# Sheet2.net
KiCad netlist of a schematic drawn in Altium Designer
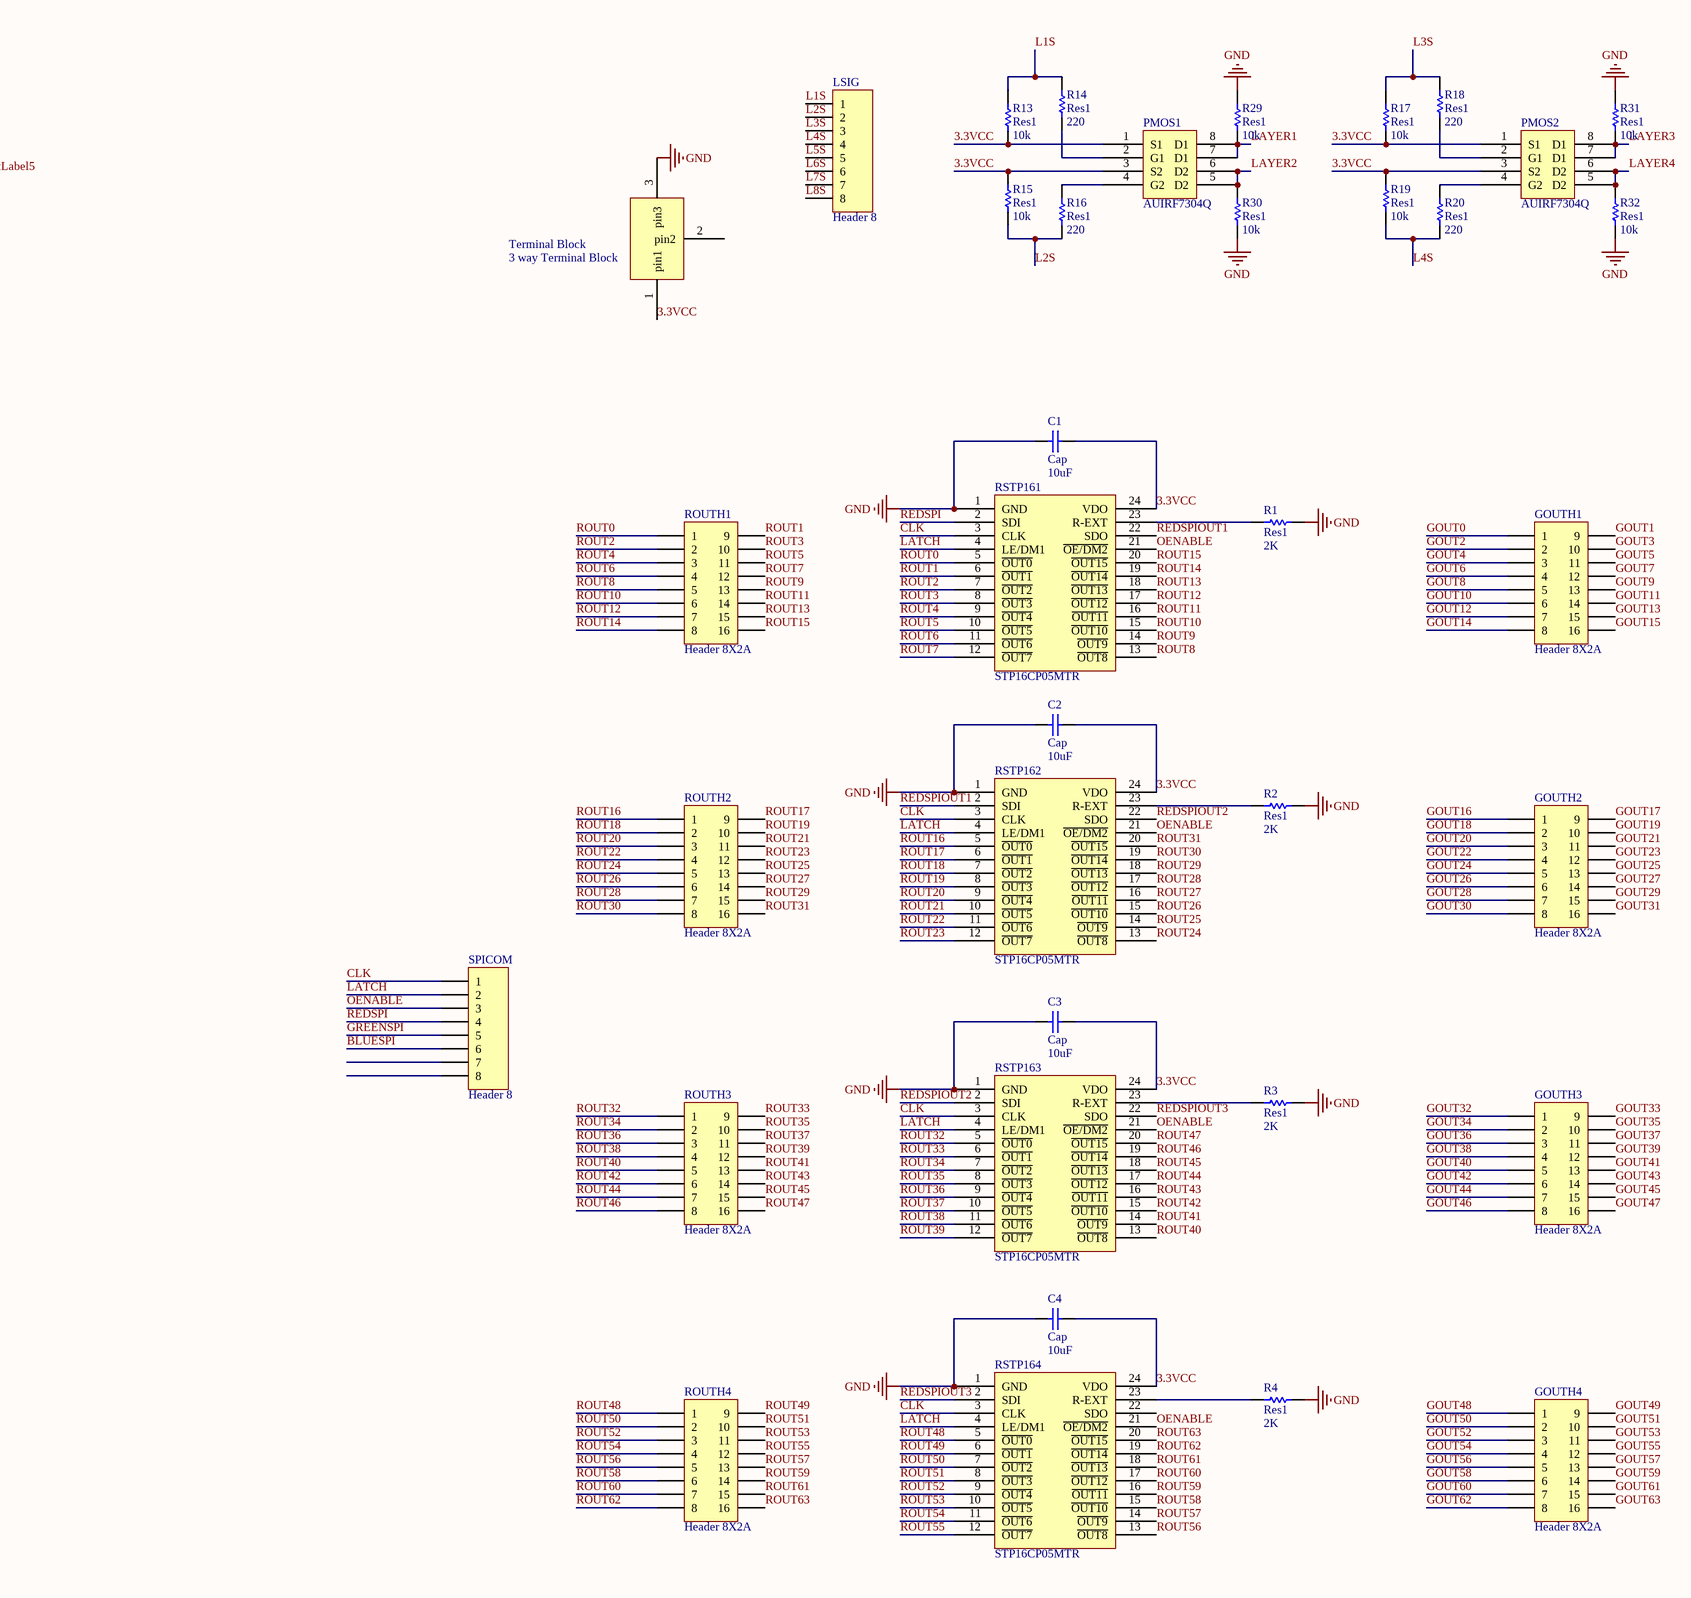
[diagram p0: Sheet2.SchDoc, left]
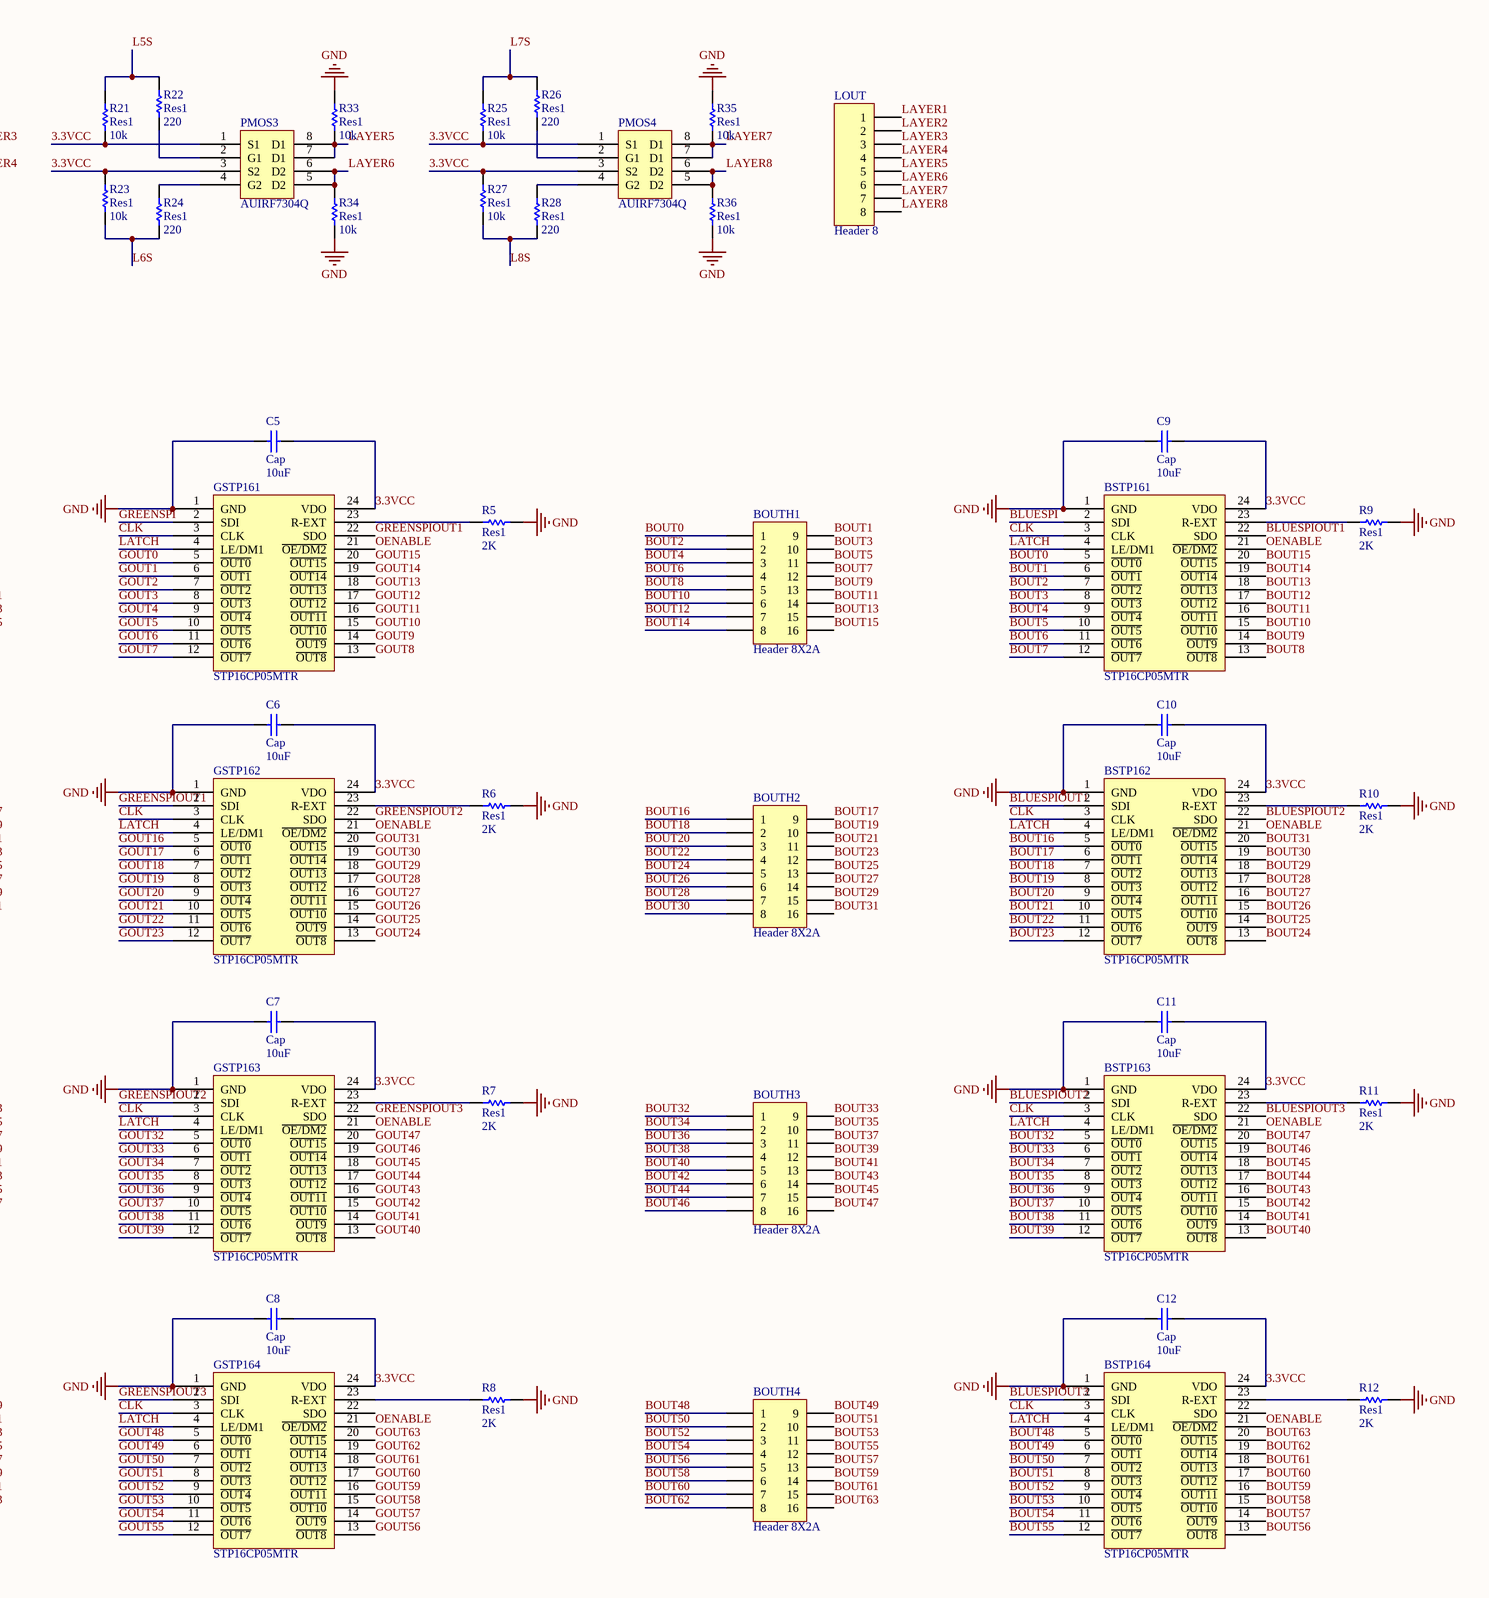
[diagram p1: Sheet2.SchDoc, right]

(export (version "E")
  (design (tool "Eeschema 10.0.6"))
  (components
    (comp (ref "BOUTH1")
      (value "Header 8X2A")
      (footprint "HDR2X8_CEN")
      (description "Header, 8-Pin, Dual row")
      (fields (field (name "PUBLISHER") "Altium Limited"))
      (libsource (lib "Miscellaneous Connectors") (part "Header 8X2A"))
    )
    (comp (ref "BOUTH2")
      (value "Header 8X2A")
      (footprint "HDR2X8_CEN")
      (description "Header, 8-Pin, Dual row")
      (fields (field (name "PUBLISHER") "Altium Limited"))
      (libsource (lib "Miscellaneous Connectors") (part "Header 8X2A"))
    )
    (comp (ref "BOUTH3")
      (value "Header 8X2A")
      (footprint "HDR2X8_CEN")
      (description "Header, 8-Pin, Dual row")
      (fields (field (name "PUBLISHER") "Altium Limited"))
      (libsource (lib "Miscellaneous Connectors") (part "Header 8X2A"))
    )
    (comp (ref "BOUTH4")
      (value "Header 8X2A")
      (footprint "HDR2X8_CEN")
      (description "Header, 8-Pin, Dual row")
      (fields (field (name "PUBLISHER") "Altium Limited"))
      (libsource (lib "Miscellaneous Connectors") (part "Header 8X2A"))
    )
    (comp (ref "BSTP161")
      (value "STP16CP05MTR")
      (footprint "STP16CP05MTR-24N")
      (libsource (lib "STP16CP05MTR") (part "STP16CP05MTR"))
    )
    (comp (ref "BSTP162")
      (value "STP16CP05MTR")
      (footprint "STP16CP05MTR-24N")
      (libsource (lib "STP16CP05MTR") (part "STP16CP05MTR"))
    )
    (comp (ref "BSTP163")
      (value "STP16CP05MTR")
      (footprint "STP16CP05MTR-24N")
      (libsource (lib "STP16CP05MTR") (part "STP16CP05MTR"))
    )
    (comp (ref "BSTP164")
      (value "STP16CP05MTR")
      (footprint "STP16CP05MTR-24N")
      (libsource (lib "STP16CP05MTR") (part "STP16CP05MTR"))
    )
    (comp (ref "C1")
      (value "Cap")
      (footprint "RAD-0.3")
      (description "Capacitor")
      (fields (field (name "ALTIUM_VALUE") "10uF") (field (name "PUBLISHER") "Altium Limited"))
      (libsource (lib "Miscellaneous Devices") (part "Cap"))
    )
    (comp (ref "C2")
      (value "Cap")
      (footprint "RAD-0.3")
      (description "Capacitor")
      (fields (field (name "ALTIUM_VALUE") "10uF") (field (name "PUBLISHER") "Altium Limited"))
      (libsource (lib "Miscellaneous Devices") (part "Cap"))
    )
    (comp (ref "C3")
      (value "Cap")
      (footprint "RAD-0.3")
      (description "Capacitor")
      (fields (field (name "ALTIUM_VALUE") "10uF") (field (name "PUBLISHER") "Altium Limited"))
      (libsource (lib "Miscellaneous Devices") (part "Cap"))
    )
    (comp (ref "C4")
      (value "Cap")
      (footprint "RAD-0.3")
      (description "Capacitor")
      (fields (field (name "ALTIUM_VALUE") "10uF") (field (name "PUBLISHER") "Altium Limited"))
      (libsource (lib "Miscellaneous Devices") (part "Cap"))
    )
    (comp (ref "C5")
      (value "Cap")
      (footprint "RAD-0.3")
      (description "Capacitor")
      (fields (field (name "ALTIUM_VALUE") "10uF") (field (name "PUBLISHER") "Altium Limited"))
      (libsource (lib "Miscellaneous Devices") (part "Cap"))
    )
    (comp (ref "C6")
      (value "Cap")
      (footprint "RAD-0.3")
      (description "Capacitor")
      (fields (field (name "ALTIUM_VALUE") "10uF") (field (name "PUBLISHER") "Altium Limited"))
      (libsource (lib "Miscellaneous Devices") (part "Cap"))
    )
    (comp (ref "C7")
      (value "Cap")
      (footprint "RAD-0.3")
      (description "Capacitor")
      (fields (field (name "ALTIUM_VALUE") "10uF") (field (name "PUBLISHER") "Altium Limited"))
      (libsource (lib "Miscellaneous Devices") (part "Cap"))
    )
    (comp (ref "C8")
      (value "Cap")
      (footprint "RAD-0.3")
      (description "Capacitor")
      (fields (field (name "ALTIUM_VALUE") "10uF") (field (name "PUBLISHER") "Altium Limited"))
      (libsource (lib "Miscellaneous Devices") (part "Cap"))
    )
    (comp (ref "C9")
      (value "Cap")
      (footprint "RAD-0.3")
      (description "Capacitor")
      (fields (field (name "ALTIUM_VALUE") "10uF") (field (name "PUBLISHER") "Altium Limited"))
      (libsource (lib "Miscellaneous Devices") (part "Cap"))
    )
    (comp (ref "C10")
      (value "Cap")
      (footprint "RAD-0.3")
      (description "Capacitor")
      (fields (field (name "ALTIUM_VALUE") "10uF") (field (name "PUBLISHER") "Altium Limited"))
      (libsource (lib "Miscellaneous Devices") (part "Cap"))
    )
    (comp (ref "C11")
      (value "Cap")
      (footprint "RAD-0.3")
      (description "Capacitor")
      (fields (field (name "ALTIUM_VALUE") "10uF") (field (name "PUBLISHER") "Altium Limited"))
      (libsource (lib "Miscellaneous Devices") (part "Cap"))
    )
    (comp (ref "C12")
      (value "Cap")
      (footprint "RAD0.2A")
      (description "Capacitor")
      (fields (field (name "ALTIUM_VALUE") "10uF") (field (name "PUBLISHER") "Altium Limited"))
      (libsource (lib "Miscellaneous Devices") (part "Cap"))
    )
    (comp (ref "GOUTH1")
      (value "Header 8X2A")
      (footprint "HDR2X8_CEN")
      (description "Header, 8-Pin, Dual row")
      (fields (field (name "PUBLISHER") "Altium Limited"))
      (libsource (lib "Miscellaneous Connectors") (part "Header 8X2A"))
    )
    (comp (ref "GOUTH2")
      (value "Header 8X2A")
      (footprint "HDR2X8_CEN")
      (description "Header, 8-Pin, Dual row")
      (fields (field (name "PUBLISHER") "Altium Limited"))
      (libsource (lib "Miscellaneous Connectors") (part "Header 8X2A"))
    )
    (comp (ref "GOUTH3")
      (value "Header 8X2A")
      (footprint "HDR2X8_CEN")
      (description "Header, 8-Pin, Dual row")
      (fields (field (name "PUBLISHER") "Altium Limited"))
      (libsource (lib "Miscellaneous Connectors") (part "Header 8X2A"))
    )
    (comp (ref "GOUTH4")
      (value "Header 8X2A")
      (footprint "HDR2X8_CEN")
      (description "Header, 8-Pin, Dual row")
      (fields (field (name "PUBLISHER") "Altium Limited"))
      (libsource (lib "Miscellaneous Connectors") (part "Header 8X2A"))
    )
    (comp (ref "GSTP161")
      (value "STP16CP05MTR")
      (footprint "STP16CP05MTR-24N")
      (libsource (lib "STP16CP05MTR") (part "STP16CP05MTR"))
    )
    (comp (ref "GSTP162")
      (value "STP16CP05MTR")
      (footprint "STP16CP05MTR-24N")
      (libsource (lib "STP16CP05MTR") (part "STP16CP05MTR"))
    )
    (comp (ref "GSTP163")
      (value "STP16CP05MTR")
      (footprint "STP16CP05MTR-24N")
      (libsource (lib "STP16CP05MTR") (part "STP16CP05MTR"))
    )
    (comp (ref "GSTP164")
      (value "STP16CP05MTR")
      (footprint "STP16CP05MTR-24N")
      (libsource (lib "STP16CP05MTR") (part "STP16CP05MTR"))
    )
    (comp (ref "LOUT")
      (value "Header 8")
      (footprint "HDR1X8")
      (description "Header, 8-Pin")
      (fields (field (name "PUBLISHER") "Altium Limited"))
      (libsource (lib "Miscellaneous Connectors") (part "Header 8"))
    )
    (comp (ref "LSIG")
      (value "Header 8")
      (footprint "HDR1X8")
      (description "Header, 8-Pin")
      (fields (field (name "PUBLISHER") "Altium Limited"))
      (libsource (lib "") (part "Header 8_1"))
    )
    (comp (ref "PMOS1")
      (value "AUIRF7304Q")
      (footprint "AUIRF7304Q")
      (libsource (lib "AUIRF7304Q") (part "Component_1"))
    )
    (comp (ref "PMOS2")
      (value "AUIRF7304Q")
      (footprint "AUIRF7304Q")
      (libsource (lib "AUIRF7304Q") (part "Component_1"))
    )
    (comp (ref "PMOS3")
      (value "AUIRF7304Q")
      (footprint "AUIRF7304Q")
      (libsource (lib "AUIRF7304Q") (part "Component_1"))
    )
    (comp (ref "PMOS4")
      (value "AUIRF7304Q")
      (footprint "AUIRF7304Q")
      (libsource (lib "AUIRF7304Q") (part "Component_1"))
    )
    (comp (ref "R1")
      (value "Res1")
      (footprint "AXIAL-0.3")
      (description "Resistor")
      (fields (field (name "ALTIUM_VALUE") "2K") (field (name "PUBLISHER") "Altium Limited"))
      (libsource (lib "Miscellaneous Devices") (part "Res1"))
    )
    (comp (ref "R2")
      (value "Res1")
      (footprint "AXIAL-0.3")
      (description "Resistor")
      (fields (field (name "ALTIUM_VALUE") "2K") (field (name "PUBLISHER") "Altium Limited"))
      (libsource (lib "Miscellaneous Devices") (part "Res1"))
    )
    (comp (ref "R3")
      (value "Res1")
      (footprint "AXIAL-0.3")
      (description "Resistor")
      (fields (field (name "ALTIUM_VALUE") "2K") (field (name "PUBLISHER") "Altium Limited"))
      (libsource (lib "Miscellaneous Devices") (part "Res1"))
    )
    (comp (ref "R4")
      (value "Res1")
      (footprint "AXIAL-0.3")
      (description "Resistor")
      (fields (field (name "ALTIUM_VALUE") "2K") (field (name "PUBLISHER") "Altium Limited"))
      (libsource (lib "Miscellaneous Devices") (part "Res1"))
    )
    (comp (ref "R5")
      (value "Res1")
      (footprint "AXIAL-0.3")
      (description "Resistor")
      (fields (field (name "ALTIUM_VALUE") "2K") (field (name "PUBLISHER") "Altium Limited"))
      (libsource (lib "Miscellaneous Devices") (part "Res1"))
    )
    (comp (ref "R6")
      (value "Res1")
      (footprint "AXIAL-0.3")
      (description "Resistor")
      (fields (field (name "ALTIUM_VALUE") "2K") (field (name "PUBLISHER") "Altium Limited"))
      (libsource (lib "Miscellaneous Devices") (part "Res1"))
    )
    (comp (ref "R7")
      (value "Res1")
      (footprint "AXIAL-0.3")
      (description "Resistor")
      (fields (field (name "ALTIUM_VALUE") "2K") (field (name "PUBLISHER") "Altium Limited"))
      (libsource (lib "Miscellaneous Devices") (part "Res1"))
    )
    (comp (ref "R8")
      (value "Res1")
      (footprint "AXIAL-0.3")
      (description "Resistor")
      (fields (field (name "ALTIUM_VALUE") "2K") (field (name "PUBLISHER") "Altium Limited"))
      (libsource (lib "Miscellaneous Devices") (part "Res1"))
    )
    (comp (ref "R9")
      (value "Res1")
      (footprint "AXIAL-0.3")
      (description "Resistor")
      (fields (field (name "ALTIUM_VALUE") "2K") (field (name "PUBLISHER") "Altium Limited"))
      (libsource (lib "Miscellaneous Devices") (part "Res1"))
    )
    (comp (ref "R10")
      (value "Res1")
      (footprint "AXIAL-0.3")
      (description "Resistor")
      (fields (field (name "ALTIUM_VALUE") "2K") (field (name "PUBLISHER") "Altium Limited"))
      (libsource (lib "Miscellaneous Devices") (part "Res1"))
    )
    (comp (ref "R11")
      (value "Res1")
      (footprint "AXIAL-0.3")
      (description "Resistor")
      (fields (field (name "ALTIUM_VALUE") "2K") (field (name "PUBLISHER") "Altium Limited"))
      (libsource (lib "Miscellaneous Devices") (part "Res1"))
    )
    (comp (ref "R12")
      (value "Res1")
      (footprint "AXIAL0.4")
      (description "Resistor")
      (fields (field (name "ALTIUM_VALUE") "2K") (field (name "PUBLISHER") "Altium Limited"))
      (libsource (lib "Miscellaneous Devices") (part "Res1"))
    )
    (comp (ref "R13")
      (value "Res1")
      (footprint "AXIAL-0.3")
      (description "Resistor")
      (fields (field (name "ALTIUM_VALUE") "10k") (field (name "PUBLISHER") "Altium Limited"))
      (libsource (lib "Miscellaneous Devices") (part "Res1"))
    )
    (comp (ref "R14")
      (value "Res1")
      (footprint "AXIAL-0.3")
      (description "Resistor")
      (fields (field (name "ALTIUM_VALUE") "220") (field (name "PUBLISHER") "Altium Limited"))
      (libsource (lib "Miscellaneous Devices") (part "Res1"))
    )
    (comp (ref "R15")
      (value "Res1")
      (footprint "AXIAL-0.3")
      (description "Resistor")
      (fields (field (name "ALTIUM_VALUE") "10k") (field (name "PUBLISHER") "Altium Limited"))
      (libsource (lib "Miscellaneous Devices") (part "Res1"))
    )
    (comp (ref "R16")
      (value "Res1")
      (footprint "AXIAL-0.3")
      (description "Resistor")
      (fields (field (name "ALTIUM_VALUE") "220") (field (name "PUBLISHER") "Altium Limited"))
      (libsource (lib "Miscellaneous Devices") (part "Res1"))
    )
    (comp (ref "R17")
      (value "Res1")
      (footprint "AXIAL-0.3")
      (description "Resistor")
      (fields (field (name "ALTIUM_VALUE") "10k") (field (name "PUBLISHER") "Altium Limited"))
      (libsource (lib "Miscellaneous Devices") (part "Res1"))
    )
    (comp (ref "R18")
      (value "Res1")
      (footprint "AXIAL-0.3")
      (description "Resistor")
      (fields (field (name "ALTIUM_VALUE") "220") (field (name "PUBLISHER") "Altium Limited"))
      (libsource (lib "Miscellaneous Devices") (part "Res1"))
    )
    (comp (ref "R19")
      (value "Res1")
      (footprint "AXIAL-0.3")
      (description "Resistor")
      (fields (field (name "ALTIUM_VALUE") "10k") (field (name "PUBLISHER") "Altium Limited"))
      (libsource (lib "Miscellaneous Devices") (part "Res1"))
    )
    (comp (ref "R20")
      (value "Res1")
      (footprint "AXIAL-0.3")
      (description "Resistor")
      (fields (field (name "ALTIUM_VALUE") "220") (field (name "PUBLISHER") "Altium Limited"))
      (libsource (lib "Miscellaneous Devices") (part "Res1"))
    )
    (comp (ref "R21")
      (value "Res1")
      (footprint "AXIAL-0.3")
      (description "Resistor")
      (fields (field (name "ALTIUM_VALUE") "10k") (field (name "PUBLISHER") "Altium Limited"))
      (libsource (lib "Miscellaneous Devices") (part "Res1"))
    )
    (comp (ref "R22")
      (value "Res1")
      (footprint "AXIAL-0.3")
      (description "Resistor")
      (fields (field (name "ALTIUM_VALUE") "220") (field (name "PUBLISHER") "Altium Limited"))
      (libsource (lib "Miscellaneous Devices") (part "Res1"))
    )
    (comp (ref "R23")
      (value "Res1")
      (footprint "AXIAL-0.3")
      (description "Resistor")
      (fields (field (name "ALTIUM_VALUE") "10k") (field (name "PUBLISHER") "Altium Limited"))
      (libsource (lib "Miscellaneous Devices") (part "Res1"))
    )
    (comp (ref "R24")
      (value "Res1")
      (footprint "AXIAL-0.3")
      (description "Resistor")
      (fields (field (name "ALTIUM_VALUE") "220") (field (name "PUBLISHER") "Altium Limited"))
      (libsource (lib "Miscellaneous Devices") (part "Res1"))
    )
    (comp (ref "R25")
      (value "Res1")
      (footprint "AXIAL-0.3")
      (description "Resistor")
      (fields (field (name "ALTIUM_VALUE") "10k") (field (name "PUBLISHER") "Altium Limited"))
      (libsource (lib "Miscellaneous Devices") (part "Res1"))
    )
    (comp (ref "R26")
      (value "Res1")
      (footprint "AXIAL-0.3")
      (description "Resistor")
      (fields (field (name "ALTIUM_VALUE") "220") (field (name "PUBLISHER") "Altium Limited"))
      (libsource (lib "Miscellaneous Devices") (part "Res1"))
    )
    (comp (ref "R27")
      (value "Res1")
      (footprint "AXIAL-0.3")
      (description "Resistor")
      (fields (field (name "ALTIUM_VALUE") "10k") (field (name "PUBLISHER") "Altium Limited"))
      (libsource (lib "Miscellaneous Devices") (part "Res1"))
    )
    (comp (ref "R28")
      (value "Res1")
      (footprint "AXIAL-0.3")
      (description "Resistor")
      (fields (field (name "ALTIUM_VALUE") "220") (field (name "PUBLISHER") "Altium Limited"))
      (libsource (lib "Miscellaneous Devices") (part "Res1"))
    )
    (comp (ref "R29")
      (value "Res1")
      (footprint "AXIAL-0.3")
      (description "Resistor")
      (fields (field (name "ALTIUM_VALUE") "10k") (field (name "PUBLISHER") "Altium Limited"))
      (libsource (lib "Miscellaneous Devices") (part "Res1"))
    )
    (comp (ref "R30")
      (value "Res1")
      (footprint "AXIAL-0.3")
      (description "Resistor")
      (fields (field (name "ALTIUM_VALUE") "10k") (field (name "PUBLISHER") "Altium Limited"))
      (libsource (lib "Miscellaneous Devices") (part "Res1"))
    )
    (comp (ref "R31")
      (value "Res1")
      (footprint "AXIAL-0.3")
      (description "Resistor")
      (fields (field (name "ALTIUM_VALUE") "10k") (field (name "PUBLISHER") "Altium Limited"))
      (libsource (lib "Miscellaneous Devices") (part "Res1"))
    )
    (comp (ref "R32")
      (value "Res1")
      (footprint "AXIAL-0.3")
      (description "Resistor")
      (fields (field (name "ALTIUM_VALUE") "10k") (field (name "PUBLISHER") "Altium Limited"))
      (libsource (lib "Miscellaneous Devices") (part "Res1"))
    )
    (comp (ref "R33")
      (value "Res1")
      (footprint "AXIAL-0.3")
      (description "Resistor")
      (fields (field (name "ALTIUM_VALUE") "10k") (field (name "PUBLISHER") "Altium Limited"))
      (libsource (lib "Miscellaneous Devices") (part "Res1"))
    )
    (comp (ref "R34")
      (value "Res1")
      (footprint "AXIAL-0.3")
      (description "Resistor")
      (fields (field (name "ALTIUM_VALUE") "10k") (field (name "PUBLISHER") "Altium Limited"))
      (libsource (lib "Miscellaneous Devices") (part "Res1"))
    )
    (comp (ref "R35")
      (value "Res1")
      (footprint "AXIAL-0.3")
      (description "Resistor")
      (fields (field (name "ALTIUM_VALUE") "10k") (field (name "PUBLISHER") "Altium Limited"))
      (libsource (lib "Miscellaneous Devices") (part "Res1"))
    )
    (comp (ref "R36")
      (value "Res1")
      (footprint "AXIAL-0.3")
      (description "Resistor")
      (fields (field (name "ALTIUM_VALUE") "10k") (field (name "PUBLISHER") "Altium Limited"))
      (libsource (lib "Miscellaneous Devices") (part "Res1"))
    )
    (comp (ref "ROUTH1")
      (value "Header 8X2A")
      (footprint "HDR2X8_CEN")
      (description "Header, 8-Pin, Dual row")
      (fields (field (name "PUBLISHER") "Altium Limited"))
      (libsource (lib "Miscellaneous Connectors") (part "Header 8X2A"))
    )
    (comp (ref "ROUTH2")
      (value "Header 8X2A")
      (footprint "HDR2X8_CEN")
      (description "Header, 8-Pin, Dual row")
      (fields (field (name "PUBLISHER") "Altium Limited"))
      (libsource (lib "Miscellaneous Connectors") (part "Header 8X2A"))
    )
    (comp (ref "ROUTH3")
      (value "Header 8X2A")
      (footprint "HDR2X8_CEN")
      (description "Header, 8-Pin, Dual row")
      (fields (field (name "PUBLISHER") "Altium Limited"))
      (libsource (lib "Miscellaneous Connectors") (part "Header 8X2A"))
    )
    (comp (ref "ROUTH4")
      (value "Header 8X2A")
      (footprint "HDR2X8_CEN")
      (description "Header, 8-Pin, Dual row")
      (fields (field (name "PUBLISHER") "Altium Limited"))
      (libsource (lib "Miscellaneous Connectors") (part "Header 8X2A"))
    )
    (comp (ref "RSTP161")
      (value "STP16CP05MTR")
      (footprint "STP16CP05MTR-24N")
      (libsource (lib "STP16CP05MTR") (part "STP16CP05MTR"))
    )
    (comp (ref "RSTP162")
      (value "STP16CP05MTR")
      (footprint "STP16CP05MTR-24N")
      (libsource (lib "STP16CP05MTR") (part "STP16CP05MTR"))
    )
    (comp (ref "RSTP163")
      (value "STP16CP05MTR")
      (footprint "STP16CP05MTR-24N")
      (libsource (lib "STP16CP05MTR") (part "STP16CP05MTR"))
    )
    (comp (ref "RSTP164")
      (value "STP16CP05MTR")
      (footprint "STP16CP05MTR-24N")
      (libsource (lib "STP16CP05MTR") (part "STP16CP05MTR"))
    )
    (comp (ref "SPICOM")
      (value "Header 8")
      (footprint "HDR1X8")
      (description "Header, 8-Pin")
      (fields (field (name "PUBLISHER") "Altium Limited"))
      (libsource (lib "") (part "Header 8_1"))
    )
    (comp (ref "Terminal Block")
      (value "3 way Terminal Block")
      (footprint "PCTB3N")
      (libsource (lib "Terminal Block") (part "Component_1"))
    )
  )
  (nets
    (net (code "1") (name "/3.3VCC") (class "Default")
      (node (ref "BSTP161") (pin "24") (pinfunction "VDO_24") (pintype "passive"))
      (node (ref "BSTP162") (pin "24") (pinfunction "VDO_24") (pintype "passive"))
      (node (ref "BSTP163") (pin "24") (pinfunction "VDO_24") (pintype "passive"))
      (node (ref "BSTP164") (pin "24") (pinfunction "VDO_24") (pintype "passive"))
      (node (ref "C1") (pin "2") (pinfunction "2_2") (pintype "passive"))
      (node (ref "C10") (pin "2") (pinfunction "2_2") (pintype "passive"))
      (node (ref "C11") (pin "2") (pinfunction "2_2") (pintype "passive"))
      (node (ref "C12") (pin "2") (pinfunction "2_2") (pintype "passive"))
      (node (ref "C2") (pin "2") (pinfunction "2_2") (pintype "passive"))
      (node (ref "C3") (pin "2") (pinfunction "2_2") (pintype "passive"))
      (node (ref "C4") (pin "2") (pinfunction "2_2") (pintype "passive"))
      (node (ref "C5") (pin "2") (pinfunction "2_2") (pintype "passive"))
      (node (ref "C6") (pin "2") (pinfunction "2_2") (pintype "passive"))
      (node (ref "C7") (pin "2") (pinfunction "2_2") (pintype "passive"))
      (node (ref "C8") (pin "2") (pinfunction "2_2") (pintype "passive"))
      (node (ref "C9") (pin "2") (pinfunction "2_2") (pintype "passive"))
      (node (ref "GSTP161") (pin "24") (pinfunction "VDO_24") (pintype "passive"))
      (node (ref "GSTP162") (pin "24") (pinfunction "VDO_24") (pintype "passive"))
      (node (ref "GSTP163") (pin "24") (pinfunction "VDO_24") (pintype "passive"))
      (node (ref "GSTP164") (pin "24") (pinfunction "VDO_24") (pintype "passive"))
      (node (ref "PMOS1") (pin "1") (pinfunction "S1_1") (pintype "passive"))
      (node (ref "PMOS1") (pin "3") (pinfunction "S2_3") (pintype "passive"))
      (node (ref "PMOS2") (pin "1") (pinfunction "S1_1") (pintype "passive"))
      (node (ref "PMOS2") (pin "3") (pinfunction "S2_3") (pintype "passive"))
      (node (ref "PMOS3") (pin "1") (pinfunction "S1_1") (pintype "passive"))
      (node (ref "PMOS3") (pin "3") (pinfunction "S2_3") (pintype "passive"))
      (node (ref "PMOS4") (pin "1") (pinfunction "S1_1") (pintype "passive"))
      (node (ref "PMOS4") (pin "3") (pinfunction "S2_3") (pintype "passive"))
      (node (ref "R13") (pin "2") (pinfunction "2_2") (pintype "passive"))
      (node (ref "R15") (pin "1") (pinfunction "1_1") (pintype "passive"))
      (node (ref "R17") (pin "2") (pinfunction "2_2") (pintype "passive"))
      (node (ref "R19") (pin "1") (pinfunction "1_1") (pintype "passive"))
      (node (ref "R21") (pin "2") (pinfunction "2_2") (pintype "passive"))
      (node (ref "R23") (pin "1") (pinfunction "1_1") (pintype "passive"))
      (node (ref "R25") (pin "2") (pinfunction "2_2") (pintype "passive"))
      (node (ref "R27") (pin "1") (pinfunction "1_1") (pintype "passive"))
      (node (ref "RSTP161") (pin "24") (pinfunction "VDO_24") (pintype "passive"))
      (node (ref "RSTP162") (pin "24") (pinfunction "VDO_24") (pintype "passive"))
      (node (ref "RSTP163") (pin "24") (pinfunction "VDO_24") (pintype "passive"))
      (node (ref "RSTP164") (pin "24") (pinfunction "VDO_24") (pintype "passive"))
      (node (ref "Terminal Block") (pin "1") (pinfunction "pin1_1") (pintype "passive"))
    )
    (net (code "2") (name "/BLUESPI") (class "Default")
      (node (ref "BSTP161") (pin "2") (pinfunction "SDI_2") (pintype "passive"))
      (node (ref "SPICOM") (pin "6") (pinfunction "6_6") (pintype "passive"))
    )
    (net (code "3") (name "/BLUESPIOUT1") (class "Default")
      (node (ref "BSTP161") (pin "22") (pinfunction "SDO_22") (pintype "passive"))
      (node (ref "BSTP162") (pin "2") (pinfunction "SDI_2") (pintype "passive"))
    )
    (net (code "4") (name "/BLUESPIOUT2") (class "Default")
      (node (ref "BSTP162") (pin "22") (pinfunction "SDO_22") (pintype "passive"))
      (node (ref "BSTP163") (pin "2") (pinfunction "SDI_2") (pintype "passive"))
    )
    (net (code "5") (name "/BLUESPIOUT3") (class "Default")
      (node (ref "BSTP163") (pin "22") (pinfunction "SDO_22") (pintype "passive"))
      (node (ref "BSTP164") (pin "2") (pinfunction "SDI_2") (pintype "passive"))
    )
    (net (code "6") (name "/BOUT0") (class "Default")
      (node (ref "BOUTH1") (pin "1") (pinfunction "1_1") (pintype "passive"))
      (node (ref "BSTP161") (pin "5") (pinfunction "~{OUT0}_5") (pintype "passive"))
    )
    (net (code "7") (name "/BOUT1") (class "Default")
      (node (ref "BOUTH1") (pin "9") (pinfunction "9_9") (pintype "passive"))
      (node (ref "BSTP161") (pin "6") (pinfunction "~{OUT1}_6") (pintype "passive"))
    )
    (net (code "8") (name "/BOUT2") (class "Default")
      (node (ref "BOUTH1") (pin "2") (pinfunction "2_2") (pintype "passive"))
      (node (ref "BSTP161") (pin "7") (pinfunction "~{OUT2}_7") (pintype "passive"))
    )
    (net (code "9") (name "/BOUT3") (class "Default")
      (node (ref "BOUTH1") (pin "10") (pinfunction "10_10") (pintype "passive"))
      (node (ref "BSTP161") (pin "8") (pinfunction "~{OUT3}_8") (pintype "passive"))
    )
    (net (code "10") (name "/BOUT4") (class "Default")
      (node (ref "BOUTH1") (pin "3") (pinfunction "3_3") (pintype "passive"))
      (node (ref "BSTP161") (pin "9") (pinfunction "~{OUT4}_9") (pintype "passive"))
    )
    (net (code "11") (name "/BOUT5") (class "Default")
      (node (ref "BOUTH1") (pin "11") (pinfunction "11_11") (pintype "passive"))
      (node (ref "BSTP161") (pin "10") (pinfunction "~{OUT5}_10") (pintype "passive"))
    )
    (net (code "12") (name "/BOUT6") (class "Default")
      (node (ref "BOUTH1") (pin "4") (pinfunction "4_4") (pintype "passive"))
      (node (ref "BSTP161") (pin "11") (pinfunction "~{OUT6}_11") (pintype "passive"))
    )
    (net (code "13") (name "/BOUT7") (class "Default")
      (node (ref "BOUTH1") (pin "12") (pinfunction "12_12") (pintype "passive"))
      (node (ref "BSTP161") (pin "12") (pinfunction "~{OUT7}_12") (pintype "passive"))
    )
    (net (code "14") (name "/BOUT8") (class "Default")
      (node (ref "BOUTH1") (pin "5") (pinfunction "5_5") (pintype "passive"))
      (node (ref "BSTP161") (pin "13") (pinfunction "~{OUT8}_13") (pintype "passive"))
    )
    (net (code "15") (name "/BOUT9") (class "Default")
      (node (ref "BOUTH1") (pin "13") (pinfunction "13_13") (pintype "passive"))
      (node (ref "BSTP161") (pin "14") (pinfunction "~{OUT9}_14") (pintype "passive"))
    )
    (net (code "16") (name "/BOUT10") (class "Default")
      (node (ref "BOUTH1") (pin "6") (pinfunction "6_6") (pintype "passive"))
      (node (ref "BSTP161") (pin "15") (pinfunction "~{OUT10}_15") (pintype "passive"))
    )
    (net (code "17") (name "/BOUT11") (class "Default")
      (node (ref "BOUTH1") (pin "14") (pinfunction "14_14") (pintype "passive"))
      (node (ref "BSTP161") (pin "16") (pinfunction "~{OUT11}_16") (pintype "passive"))
    )
    (net (code "18") (name "/BOUT12") (class "Default")
      (node (ref "BOUTH1") (pin "7") (pinfunction "7_7") (pintype "passive"))
      (node (ref "BSTP161") (pin "17") (pinfunction "~{OUT12}_17") (pintype "passive"))
    )
    (net (code "19") (name "/BOUT13") (class "Default")
      (node (ref "BOUTH1") (pin "15") (pinfunction "15_15") (pintype "passive"))
      (node (ref "BSTP161") (pin "18") (pinfunction "~{OUT13}_18") (pintype "passive"))
    )
    (net (code "20") (name "/BOUT14") (class "Default")
      (node (ref "BOUTH1") (pin "8") (pinfunction "8_8") (pintype "passive"))
      (node (ref "BSTP161") (pin "19") (pinfunction "~{OUT14}_19") (pintype "passive"))
    )
    (net (code "21") (name "/BOUT15") (class "Default")
      (node (ref "BOUTH1") (pin "16") (pinfunction "16_16") (pintype "passive"))
      (node (ref "BSTP161") (pin "20") (pinfunction "~{OUT15}_20") (pintype "passive"))
    )
    (net (code "22") (name "/BOUT16") (class "Default")
      (node (ref "BOUTH2") (pin "1") (pinfunction "1_1") (pintype "passive"))
      (node (ref "BSTP162") (pin "5") (pinfunction "~{OUT0}_5") (pintype "passive"))
    )
    (net (code "23") (name "/BOUT17") (class "Default")
      (node (ref "BOUTH2") (pin "9") (pinfunction "9_9") (pintype "passive"))
      (node (ref "BSTP162") (pin "6") (pinfunction "~{OUT1}_6") (pintype "passive"))
    )
    (net (code "24") (name "/BOUT18") (class "Default")
      (node (ref "BOUTH2") (pin "2") (pinfunction "2_2") (pintype "passive"))
      (node (ref "BSTP162") (pin "7") (pinfunction "~{OUT2}_7") (pintype "passive"))
    )
    (net (code "25") (name "/BOUT19") (class "Default")
      (node (ref "BOUTH2") (pin "10") (pinfunction "10_10") (pintype "passive"))
      (node (ref "BSTP162") (pin "8") (pinfunction "~{OUT3}_8") (pintype "passive"))
    )
    (net (code "26") (name "/BOUT20") (class "Default")
      (node (ref "BOUTH2") (pin "3") (pinfunction "3_3") (pintype "passive"))
      (node (ref "BSTP162") (pin "9") (pinfunction "~{OUT4}_9") (pintype "passive"))
    )
    (net (code "27") (name "/BOUT21") (class "Default")
      (node (ref "BOUTH2") (pin "11") (pinfunction "11_11") (pintype "passive"))
      (node (ref "BSTP162") (pin "10") (pinfunction "~{OUT5}_10") (pintype "passive"))
    )
    (net (code "28") (name "/BOUT22") (class "Default")
      (node (ref "BOUTH2") (pin "4") (pinfunction "4_4") (pintype "passive"))
      (node (ref "BSTP162") (pin "11") (pinfunction "~{OUT6}_11") (pintype "passive"))
    )
    (net (code "29") (name "/BOUT23") (class "Default")
      (node (ref "BOUTH2") (pin "12") (pinfunction "12_12") (pintype "passive"))
      (node (ref "BSTP162") (pin "12") (pinfunction "~{OUT7}_12") (pintype "passive"))
    )
    (net (code "30") (name "/BOUT24") (class "Default")
      (node (ref "BOUTH2") (pin "5") (pinfunction "5_5") (pintype "passive"))
      (node (ref "BSTP162") (pin "13") (pinfunction "~{OUT8}_13") (pintype "passive"))
    )
    (net (code "31") (name "/BOUT25") (class "Default")
      (node (ref "BOUTH2") (pin "13") (pinfunction "13_13") (pintype "passive"))
      (node (ref "BSTP162") (pin "14") (pinfunction "~{OUT9}_14") (pintype "passive"))
    )
    (net (code "32") (name "/BOUT26") (class "Default")
      (node (ref "BOUTH2") (pin "6") (pinfunction "6_6") (pintype "passive"))
      (node (ref "BSTP162") (pin "15") (pinfunction "~{OUT10}_15") (pintype "passive"))
    )
    (net (code "33") (name "/BOUT27") (class "Default")
      (node (ref "BOUTH2") (pin "14") (pinfunction "14_14") (pintype "passive"))
      (node (ref "BSTP162") (pin "16") (pinfunction "~{OUT11}_16") (pintype "passive"))
    )
    (net (code "34") (name "/BOUT28") (class "Default")
      (node (ref "BOUTH2") (pin "7") (pinfunction "7_7") (pintype "passive"))
      (node (ref "BSTP162") (pin "17") (pinfunction "~{OUT12}_17") (pintype "passive"))
    )
    (net (code "35") (name "/BOUT29") (class "Default")
      (node (ref "BOUTH2") (pin "15") (pinfunction "15_15") (pintype "passive"))
      (node (ref "BSTP162") (pin "18") (pinfunction "~{OUT13}_18") (pintype "passive"))
    )
    (net (code "36") (name "/BOUT30") (class "Default")
      (node (ref "BOUTH2") (pin "8") (pinfunction "8_8") (pintype "passive"))
      (node (ref "BSTP162") (pin "19") (pinfunction "~{OUT14}_19") (pintype "passive"))
    )
    (net (code "37") (name "/BOUT31") (class "Default")
      (node (ref "BOUTH2") (pin "16") (pinfunction "16_16") (pintype "passive"))
      (node (ref "BSTP162") (pin "20") (pinfunction "~{OUT15}_20") (pintype "passive"))
    )
    (net (code "38") (name "/BOUT32") (class "Default")
      (node (ref "BOUTH3") (pin "1") (pinfunction "1_1") (pintype "passive"))
      (node (ref "BSTP163") (pin "5") (pinfunction "~{OUT0}_5") (pintype "passive"))
    )
    (net (code "39") (name "/BOUT33") (class "Default")
      (node (ref "BOUTH3") (pin "9") (pinfunction "9_9") (pintype "passive"))
      (node (ref "BSTP163") (pin "6") (pinfunction "~{OUT1}_6") (pintype "passive"))
    )
    (net (code "40") (name "/BOUT34") (class "Default")
      (node (ref "BOUTH3") (pin "2") (pinfunction "2_2") (pintype "passive"))
      (node (ref "BSTP163") (pin "7") (pinfunction "~{OUT2}_7") (pintype "passive"))
    )
    (net (code "41") (name "/BOUT35") (class "Default")
      (node (ref "BOUTH3") (pin "10") (pinfunction "10_10") (pintype "passive"))
      (node (ref "BSTP163") (pin "8") (pinfunction "~{OUT3}_8") (pintype "passive"))
    )
    (net (code "42") (name "/BOUT36") (class "Default")
      (node (ref "BOUTH3") (pin "3") (pinfunction "3_3") (pintype "passive"))
      (node (ref "BSTP163") (pin "9") (pinfunction "~{OUT4}_9") (pintype "passive"))
    )
    (net (code "43") (name "/BOUT37") (class "Default")
      (node (ref "BOUTH3") (pin "11") (pinfunction "11_11") (pintype "passive"))
      (node (ref "BSTP163") (pin "10") (pinfunction "~{OUT5}_10") (pintype "passive"))
    )
    (net (code "44") (name "/BOUT38") (class "Default")
      (node (ref "BOUTH3") (pin "4") (pinfunction "4_4") (pintype "passive"))
      (node (ref "BSTP163") (pin "11") (pinfunction "~{OUT6}_11") (pintype "passive"))
    )
    (net (code "45") (name "/BOUT39") (class "Default")
      (node (ref "BOUTH3") (pin "12") (pinfunction "12_12") (pintype "passive"))
      (node (ref "BSTP163") (pin "12") (pinfunction "~{OUT7}_12") (pintype "passive"))
    )
    (net (code "46") (name "/BOUT40") (class "Default")
      (node (ref "BOUTH3") (pin "5") (pinfunction "5_5") (pintype "passive"))
      (node (ref "BSTP163") (pin "13") (pinfunction "~{OUT8}_13") (pintype "passive"))
    )
    (net (code "47") (name "/BOUT41") (class "Default")
      (node (ref "BOUTH3") (pin "13") (pinfunction "13_13") (pintype "passive"))
      (node (ref "BSTP163") (pin "14") (pinfunction "~{OUT9}_14") (pintype "passive"))
    )
    (net (code "48") (name "/BOUT42") (class "Default")
      (node (ref "BOUTH3") (pin "6") (pinfunction "6_6") (pintype "passive"))
      (node (ref "BSTP163") (pin "15") (pinfunction "~{OUT10}_15") (pintype "passive"))
    )
    (net (code "49") (name "/BOUT43") (class "Default")
      (node (ref "BOUTH3") (pin "14") (pinfunction "14_14") (pintype "passive"))
      (node (ref "BSTP163") (pin "16") (pinfunction "~{OUT11}_16") (pintype "passive"))
    )
    (net (code "50") (name "/BOUT44") (class "Default")
      (node (ref "BOUTH3") (pin "7") (pinfunction "7_7") (pintype "passive"))
      (node (ref "BSTP163") (pin "17") (pinfunction "~{OUT12}_17") (pintype "passive"))
    )
    (net (code "51") (name "/BOUT45") (class "Default")
      (node (ref "BOUTH3") (pin "15") (pinfunction "15_15") (pintype "passive"))
      (node (ref "BSTP163") (pin "18") (pinfunction "~{OUT13}_18") (pintype "passive"))
    )
    (net (code "52") (name "/BOUT46") (class "Default")
      (node (ref "BOUTH3") (pin "8") (pinfunction "8_8") (pintype "passive"))
      (node (ref "BSTP163") (pin "19") (pinfunction "~{OUT14}_19") (pintype "passive"))
    )
    (net (code "53") (name "/BOUT47") (class "Default")
      (node (ref "BOUTH3") (pin "16") (pinfunction "16_16") (pintype "passive"))
      (node (ref "BSTP163") (pin "20") (pinfunction "~{OUT15}_20") (pintype "passive"))
    )
    (net (code "54") (name "/BOUT48") (class "Default")
      (node (ref "BOUTH4") (pin "1") (pinfunction "1_1") (pintype "passive"))
      (node (ref "BSTP164") (pin "5") (pinfunction "~{OUT0}_5") (pintype "passive"))
    )
    (net (code "55") (name "/BOUT49") (class "Default")
      (node (ref "BOUTH4") (pin "9") (pinfunction "9_9") (pintype "passive"))
      (node (ref "BSTP164") (pin "6") (pinfunction "~{OUT1}_6") (pintype "passive"))
    )
    (net (code "56") (name "/BOUT50") (class "Default")
      (node (ref "BOUTH4") (pin "2") (pinfunction "2_2") (pintype "passive"))
      (node (ref "BSTP164") (pin "7") (pinfunction "~{OUT2}_7") (pintype "passive"))
    )
    (net (code "57") (name "/BOUT51") (class "Default")
      (node (ref "BOUTH4") (pin "10") (pinfunction "10_10") (pintype "passive"))
      (node (ref "BSTP164") (pin "8") (pinfunction "~{OUT3}_8") (pintype "passive"))
    )
    (net (code "58") (name "/BOUT52") (class "Default")
      (node (ref "BOUTH4") (pin "3") (pinfunction "3_3") (pintype "passive"))
      (node (ref "BSTP164") (pin "9") (pinfunction "~{OUT4}_9") (pintype "passive"))
    )
    (net (code "59") (name "/BOUT53") (class "Default")
      (node (ref "BOUTH4") (pin "11") (pinfunction "11_11") (pintype "passive"))
      (node (ref "BSTP164") (pin "10") (pinfunction "~{OUT5}_10") (pintype "passive"))
    )
    (net (code "60") (name "/BOUT54") (class "Default")
      (node (ref "BOUTH4") (pin "4") (pinfunction "4_4") (pintype "passive"))
      (node (ref "BSTP164") (pin "11") (pinfunction "~{OUT6}_11") (pintype "passive"))
    )
    (net (code "61") (name "/BOUT55") (class "Default")
      (node (ref "BOUTH4") (pin "12") (pinfunction "12_12") (pintype "passive"))
      (node (ref "BSTP164") (pin "12") (pinfunction "~{OUT7}_12") (pintype "passive"))
    )
    (net (code "62") (name "/BOUT56") (class "Default")
      (node (ref "BOUTH4") (pin "5") (pinfunction "5_5") (pintype "passive"))
      (node (ref "BSTP164") (pin "13") (pinfunction "~{OUT8}_13") (pintype "passive"))
    )
    (net (code "63") (name "/BOUT57") (class "Default")
      (node (ref "BOUTH4") (pin "13") (pinfunction "13_13") (pintype "passive"))
      (node (ref "BSTP164") (pin "14") (pinfunction "~{OUT9}_14") (pintype "passive"))
    )
    (net (code "64") (name "/BOUT58") (class "Default")
      (node (ref "BOUTH4") (pin "6") (pinfunction "6_6") (pintype "passive"))
      (node (ref "BSTP164") (pin "15") (pinfunction "~{OUT10}_15") (pintype "passive"))
    )
    (net (code "65") (name "/BOUT59") (class "Default")
      (node (ref "BOUTH4") (pin "14") (pinfunction "14_14") (pintype "passive"))
      (node (ref "BSTP164") (pin "16") (pinfunction "~{OUT11}_16") (pintype "passive"))
    )
    (net (code "66") (name "/BOUT60") (class "Default")
      (node (ref "BOUTH4") (pin "7") (pinfunction "7_7") (pintype "passive"))
      (node (ref "BSTP164") (pin "17") (pinfunction "~{OUT12}_17") (pintype "passive"))
    )
    (net (code "67") (name "/BOUT61") (class "Default")
      (node (ref "BOUTH4") (pin "15") (pinfunction "15_15") (pintype "passive"))
      (node (ref "BSTP164") (pin "18") (pinfunction "~{OUT13}_18") (pintype "passive"))
    )
    (net (code "68") (name "/BOUT62") (class "Default")
      (node (ref "BOUTH4") (pin "8") (pinfunction "8_8") (pintype "passive"))
      (node (ref "BSTP164") (pin "19") (pinfunction "~{OUT14}_19") (pintype "passive"))
    )
    (net (code "69") (name "/BOUT63") (class "Default")
      (node (ref "BOUTH4") (pin "16") (pinfunction "16_16") (pintype "passive"))
      (node (ref "BSTP164") (pin "20") (pinfunction "~{OUT15}_20") (pintype "passive"))
    )
    (net (code "70") (name "/CLK") (class "Default")
      (node (ref "BSTP161") (pin "3") (pinfunction "CLK_3") (pintype "passive"))
      (node (ref "BSTP162") (pin "3") (pinfunction "CLK_3") (pintype "passive"))
      (node (ref "BSTP163") (pin "3") (pinfunction "CLK_3") (pintype "passive"))
      (node (ref "BSTP164") (pin "3") (pinfunction "CLK_3") (pintype "passive"))
      (node (ref "GSTP161") (pin "3") (pinfunction "CLK_3") (pintype "passive"))
      (node (ref "GSTP162") (pin "3") (pinfunction "CLK_3") (pintype "passive"))
      (node (ref "GSTP163") (pin "3") (pinfunction "CLK_3") (pintype "passive"))
      (node (ref "GSTP164") (pin "3") (pinfunction "CLK_3") (pintype "passive"))
      (node (ref "RSTP161") (pin "3") (pinfunction "CLK_3") (pintype "passive"))
      (node (ref "RSTP162") (pin "3") (pinfunction "CLK_3") (pintype "passive"))
      (node (ref "RSTP163") (pin "3") (pinfunction "CLK_3") (pintype "passive"))
      (node (ref "RSTP164") (pin "3") (pinfunction "CLK_3") (pintype "passive"))
      (node (ref "SPICOM") (pin "1") (pinfunction "1_1") (pintype "passive"))
    )
    (net (code "71") (name "/GOUT0") (class "Default")
      (node (ref "GOUTH1") (pin "1") (pinfunction "1_1") (pintype "passive"))
      (node (ref "GSTP161") (pin "5") (pinfunction "~{OUT0}_5") (pintype "passive"))
    )
    (net (code "72") (name "/GOUT1") (class "Default")
      (node (ref "GOUTH1") (pin "9") (pinfunction "9_9") (pintype "passive"))
      (node (ref "GSTP161") (pin "6") (pinfunction "~{OUT1}_6") (pintype "passive"))
    )
    (net (code "73") (name "/GOUT2") (class "Default")
      (node (ref "GOUTH1") (pin "2") (pinfunction "2_2") (pintype "passive"))
      (node (ref "GSTP161") (pin "7") (pinfunction "~{OUT2}_7") (pintype "passive"))
    )
    (net (code "74") (name "/GOUT3") (class "Default")
      (node (ref "GOUTH1") (pin "10") (pinfunction "10_10") (pintype "passive"))
      (node (ref "GSTP161") (pin "8") (pinfunction "~{OUT3}_8") (pintype "passive"))
    )
    (net (code "75") (name "/GOUT4") (class "Default")
      (node (ref "GOUTH1") (pin "3") (pinfunction "3_3") (pintype "passive"))
      (node (ref "GSTP161") (pin "9") (pinfunction "~{OUT4}_9") (pintype "passive"))
    )
    (net (code "76") (name "/GOUT5") (class "Default")
      (node (ref "GOUTH1") (pin "11") (pinfunction "11_11") (pintype "passive"))
      (node (ref "GSTP161") (pin "10") (pinfunction "~{OUT5}_10") (pintype "passive"))
    )
    (net (code "77") (name "/GOUT6") (class "Default")
      (node (ref "GOUTH1") (pin "4") (pinfunction "4_4") (pintype "passive"))
      (node (ref "GSTP161") (pin "11") (pinfunction "~{OUT6}_11") (pintype "passive"))
    )
    (net (code "78") (name "/GOUT7") (class "Default")
      (node (ref "GOUTH1") (pin "12") (pinfunction "12_12") (pintype "passive"))
      (node (ref "GSTP161") (pin "12") (pinfunction "~{OUT7}_12") (pintype "passive"))
    )
    (net (code "79") (name "/GOUT8") (class "Default")
      (node (ref "GOUTH1") (pin "5") (pinfunction "5_5") (pintype "passive"))
      (node (ref "GSTP161") (pin "13") (pinfunction "~{OUT8}_13") (pintype "passive"))
    )
    (net (code "80") (name "/GOUT9") (class "Default")
      (node (ref "GOUTH1") (pin "13") (pinfunction "13_13") (pintype "passive"))
      (node (ref "GSTP161") (pin "14") (pinfunction "~{OUT9}_14") (pintype "passive"))
    )
    (net (code "81") (name "/GOUT10") (class "Default")
      (node (ref "GOUTH1") (pin "6") (pinfunction "6_6") (pintype "passive"))
      (node (ref "GSTP161") (pin "15") (pinfunction "~{OUT10}_15") (pintype "passive"))
    )
    (net (code "82") (name "/GOUT11") (class "Default")
      (node (ref "GOUTH1") (pin "14") (pinfunction "14_14") (pintype "passive"))
      (node (ref "GSTP161") (pin "16") (pinfunction "~{OUT11}_16") (pintype "passive"))
    )
    (net (code "83") (name "/GOUT12") (class "Default")
      (node (ref "GOUTH1") (pin "7") (pinfunction "7_7") (pintype "passive"))
      (node (ref "GSTP161") (pin "17") (pinfunction "~{OUT12}_17") (pintype "passive"))
    )
    (net (code "84") (name "/GOUT13") (class "Default")
      (node (ref "GOUTH1") (pin "15") (pinfunction "15_15") (pintype "passive"))
      (node (ref "GSTP161") (pin "18") (pinfunction "~{OUT13}_18") (pintype "passive"))
    )
    (net (code "85") (name "/GOUT14") (class "Default")
      (node (ref "GOUTH1") (pin "8") (pinfunction "8_8") (pintype "passive"))
      (node (ref "GSTP161") (pin "19") (pinfunction "~{OUT14}_19") (pintype "passive"))
    )
    (net (code "86") (name "/GOUT15") (class "Default")
      (node (ref "GOUTH1") (pin "16") (pinfunction "16_16") (pintype "passive"))
      (node (ref "GSTP161") (pin "20") (pinfunction "~{OUT15}_20") (pintype "passive"))
    )
    (net (code "87") (name "/GOUT16") (class "Default")
      (node (ref "GOUTH2") (pin "1") (pinfunction "1_1") (pintype "passive"))
      (node (ref "GSTP162") (pin "5") (pinfunction "~{OUT0}_5") (pintype "passive"))
    )
    (net (code "88") (name "/GOUT17") (class "Default")
      (node (ref "GOUTH2") (pin "9") (pinfunction "9_9") (pintype "passive"))
      (node (ref "GSTP162") (pin "6") (pinfunction "~{OUT1}_6") (pintype "passive"))
    )
    (net (code "89") (name "/GOUT18") (class "Default")
      (node (ref "GOUTH2") (pin "2") (pinfunction "2_2") (pintype "passive"))
      (node (ref "GSTP162") (pin "7") (pinfunction "~{OUT2}_7") (pintype "passive"))
    )
    (net (code "90") (name "/GOUT19") (class "Default")
      (node (ref "GOUTH2") (pin "10") (pinfunction "10_10") (pintype "passive"))
      (node (ref "GSTP162") (pin "8") (pinfunction "~{OUT3}_8") (pintype "passive"))
    )
    (net (code "91") (name "/GOUT20") (class "Default")
      (node (ref "GOUTH2") (pin "3") (pinfunction "3_3") (pintype "passive"))
      (node (ref "GSTP162") (pin "9") (pinfunction "~{OUT4}_9") (pintype "passive"))
    )
    (net (code "92") (name "/GOUT21") (class "Default")
      (node (ref "GOUTH2") (pin "11") (pinfunction "11_11") (pintype "passive"))
      (node (ref "GSTP162") (pin "10") (pinfunction "~{OUT5}_10") (pintype "passive"))
    )
    (net (code "93") (name "/GOUT22") (class "Default")
      (node (ref "GOUTH2") (pin "4") (pinfunction "4_4") (pintype "passive"))
      (node (ref "GSTP162") (pin "11") (pinfunction "~{OUT6}_11") (pintype "passive"))
    )
    (net (code "94") (name "/GOUT23") (class "Default")
      (node (ref "GOUTH2") (pin "12") (pinfunction "12_12") (pintype "passive"))
      (node (ref "GSTP162") (pin "12") (pinfunction "~{OUT7}_12") (pintype "passive"))
    )
    (net (code "95") (name "/GOUT24") (class "Default")
      (node (ref "GOUTH2") (pin "5") (pinfunction "5_5") (pintype "passive"))
      (node (ref "GSTP162") (pin "13") (pinfunction "~{OUT8}_13") (pintype "passive"))
    )
    (net (code "96") (name "/GOUT25") (class "Default")
      (node (ref "GOUTH2") (pin "13") (pinfunction "13_13") (pintype "passive"))
      (node (ref "GSTP162") (pin "14") (pinfunction "~{OUT9}_14") (pintype "passive"))
    )
    (net (code "97") (name "/GOUT26") (class "Default")
      (node (ref "GOUTH2") (pin "6") (pinfunction "6_6") (pintype "passive"))
      (node (ref "GSTP162") (pin "15") (pinfunction "~{OUT10}_15") (pintype "passive"))
    )
    (net (code "98") (name "/GOUT27") (class "Default")
      (node (ref "GOUTH2") (pin "14") (pinfunction "14_14") (pintype "passive"))
      (node (ref "GSTP162") (pin "16") (pinfunction "~{OUT11}_16") (pintype "passive"))
    )
    (net (code "99") (name "/GOUT28") (class "Default")
      (node (ref "GOUTH2") (pin "7") (pinfunction "7_7") (pintype "passive"))
      (node (ref "GSTP162") (pin "17") (pinfunction "~{OUT12}_17") (pintype "passive"))
    )
    (net (code "100") (name "/GOUT29") (class "Default")
      (node (ref "GOUTH2") (pin "15") (pinfunction "15_15") (pintype "passive"))
      (node (ref "GSTP162") (pin "18") (pinfunction "~{OUT13}_18") (pintype "passive"))
    )
    (net (code "101") (name "/GOUT30") (class "Default")
      (node (ref "GOUTH2") (pin "8") (pinfunction "8_8") (pintype "passive"))
      (node (ref "GSTP162") (pin "19") (pinfunction "~{OUT14}_19") (pintype "passive"))
    )
    (net (code "102") (name "/GOUT31") (class "Default")
      (node (ref "GOUTH2") (pin "16") (pinfunction "16_16") (pintype "passive"))
      (node (ref "GSTP162") (pin "20") (pinfunction "~{OUT15}_20") (pintype "passive"))
    )
    (net (code "103") (name "/GOUT32") (class "Default")
      (node (ref "GOUTH3") (pin "1") (pinfunction "1_1") (pintype "passive"))
      (node (ref "GSTP163") (pin "5") (pinfunction "~{OUT0}_5") (pintype "passive"))
    )
    (net (code "104") (name "/GOUT33") (class "Default")
      (node (ref "GOUTH3") (pin "9") (pinfunction "9_9") (pintype "passive"))
      (node (ref "GSTP163") (pin "6") (pinfunction "~{OUT1}_6") (pintype "passive"))
    )
    (net (code "105") (name "/GOUT34") (class "Default")
      (node (ref "GOUTH3") (pin "2") (pinfunction "2_2") (pintype "passive"))
      (node (ref "GSTP163") (pin "7") (pinfunction "~{OUT2}_7") (pintype "passive"))
    )
    (net (code "106") (name "/GOUT35") (class "Default")
      (node (ref "GOUTH3") (pin "10") (pinfunction "10_10") (pintype "passive"))
      (node (ref "GSTP163") (pin "8") (pinfunction "~{OUT3}_8") (pintype "passive"))
    )
    (net (code "107") (name "/GOUT36") (class "Default")
      (node (ref "GOUTH3") (pin "3") (pinfunction "3_3") (pintype "passive"))
      (node (ref "GSTP163") (pin "9") (pinfunction "~{OUT4}_9") (pintype "passive"))
    )
    (net (code "108") (name "/GOUT37") (class "Default")
      (node (ref "GOUTH3") (pin "11") (pinfunction "11_11") (pintype "passive"))
      (node (ref "GSTP163") (pin "10") (pinfunction "~{OUT5}_10") (pintype "passive"))
    )
    (net (code "109") (name "/GOUT38") (class "Default")
      (node (ref "GOUTH3") (pin "4") (pinfunction "4_4") (pintype "passive"))
      (node (ref "GSTP163") (pin "11") (pinfunction "~{OUT6}_11") (pintype "passive"))
    )
    (net (code "110") (name "/GOUT39") (class "Default")
      (node (ref "GOUTH3") (pin "12") (pinfunction "12_12") (pintype "passive"))
      (node (ref "GSTP163") (pin "12") (pinfunction "~{OUT7}_12") (pintype "passive"))
    )
    (net (code "111") (name "/GOUT40") (class "Default")
      (node (ref "GOUTH3") (pin "5") (pinfunction "5_5") (pintype "passive"))
      (node (ref "GSTP163") (pin "13") (pinfunction "~{OUT8}_13") (pintype "passive"))
    )
    (net (code "112") (name "/GOUT41") (class "Default")
      (node (ref "GOUTH3") (pin "13") (pinfunction "13_13") (pintype "passive"))
      (node (ref "GSTP163") (pin "14") (pinfunction "~{OUT9}_14") (pintype "passive"))
    )
    (net (code "113") (name "/GOUT42") (class "Default")
      (node (ref "GOUTH3") (pin "6") (pinfunction "6_6") (pintype "passive"))
      (node (ref "GSTP163") (pin "15") (pinfunction "~{OUT10}_15") (pintype "passive"))
    )
    (net (code "114") (name "/GOUT43") (class "Default")
      (node (ref "GOUTH3") (pin "14") (pinfunction "14_14") (pintype "passive"))
      (node (ref "GSTP163") (pin "16") (pinfunction "~{OUT11}_16") (pintype "passive"))
    )
    (net (code "115") (name "/GOUT44") (class "Default")
      (node (ref "GOUTH3") (pin "7") (pinfunction "7_7") (pintype "passive"))
      (node (ref "GSTP163") (pin "17") (pinfunction "~{OUT12}_17") (pintype "passive"))
    )
    (net (code "116") (name "/GOUT45") (class "Default")
      (node (ref "GOUTH3") (pin "15") (pinfunction "15_15") (pintype "passive"))
      (node (ref "GSTP163") (pin "18") (pinfunction "~{OUT13}_18") (pintype "passive"))
    )
    (net (code "117") (name "/GOUT46") (class "Default")
      (node (ref "GOUTH3") (pin "8") (pinfunction "8_8") (pintype "passive"))
      (node (ref "GSTP163") (pin "19") (pinfunction "~{OUT14}_19") (pintype "passive"))
    )
    (net (code "118") (name "/GOUT47") (class "Default")
      (node (ref "GOUTH3") (pin "16") (pinfunction "16_16") (pintype "passive"))
      (node (ref "GSTP163") (pin "20") (pinfunction "~{OUT15}_20") (pintype "passive"))
    )
    (net (code "119") (name "/GOUT48") (class "Default")
      (node (ref "GOUTH4") (pin "1") (pinfunction "1_1") (pintype "passive"))
      (node (ref "GSTP164") (pin "5") (pinfunction "~{OUT0}_5") (pintype "passive"))
    )
    (net (code "120") (name "/GOUT49") (class "Default")
      (node (ref "GOUTH4") (pin "9") (pinfunction "9_9") (pintype "passive"))
      (node (ref "GSTP164") (pin "6") (pinfunction "~{OUT1}_6") (pintype "passive"))
    )
    (net (code "121") (name "/GOUT50") (class "Default")
      (node (ref "GOUTH4") (pin "2") (pinfunction "2_2") (pintype "passive"))
      (node (ref "GSTP164") (pin "7") (pinfunction "~{OUT2}_7") (pintype "passive"))
    )
    (net (code "122") (name "/GOUT51") (class "Default")
      (node (ref "GOUTH4") (pin "10") (pinfunction "10_10") (pintype "passive"))
      (node (ref "GSTP164") (pin "8") (pinfunction "~{OUT3}_8") (pintype "passive"))
    )
    (net (code "123") (name "/GOUT52") (class "Default")
      (node (ref "GOUTH4") (pin "3") (pinfunction "3_3") (pintype "passive"))
      (node (ref "GSTP164") (pin "9") (pinfunction "~{OUT4}_9") (pintype "passive"))
    )
    (net (code "124") (name "/GOUT53") (class "Default")
      (node (ref "GOUTH4") (pin "11") (pinfunction "11_11") (pintype "passive"))
      (node (ref "GSTP164") (pin "10") (pinfunction "~{OUT5}_10") (pintype "passive"))
    )
    (net (code "125") (name "/GOUT54") (class "Default")
      (node (ref "GOUTH4") (pin "4") (pinfunction "4_4") (pintype "passive"))
      (node (ref "GSTP164") (pin "11") (pinfunction "~{OUT6}_11") (pintype "passive"))
    )
    (net (code "126") (name "/GOUT55") (class "Default")
      (node (ref "GOUTH4") (pin "12") (pinfunction "12_12") (pintype "passive"))
      (node (ref "GSTP164") (pin "12") (pinfunction "~{OUT7}_12") (pintype "passive"))
    )
    (net (code "127") (name "/GOUT56") (class "Default")
      (node (ref "GOUTH4") (pin "5") (pinfunction "5_5") (pintype "passive"))
      (node (ref "GSTP164") (pin "13") (pinfunction "~{OUT8}_13") (pintype "passive"))
    )
    (net (code "128") (name "/GOUT57") (class "Default")
      (node (ref "GOUTH4") (pin "13") (pinfunction "13_13") (pintype "passive"))
      (node (ref "GSTP164") (pin "14") (pinfunction "~{OUT9}_14") (pintype "passive"))
    )
    (net (code "129") (name "/GOUT58") (class "Default")
      (node (ref "GOUTH4") (pin "6") (pinfunction "6_6") (pintype "passive"))
      (node (ref "GSTP164") (pin "15") (pinfunction "~{OUT10}_15") (pintype "passive"))
    )
    (net (code "130") (name "/GOUT59") (class "Default")
      (node (ref "GOUTH4") (pin "14") (pinfunction "14_14") (pintype "passive"))
      (node (ref "GSTP164") (pin "16") (pinfunction "~{OUT11}_16") (pintype "passive"))
    )
    (net (code "131") (name "/GOUT60") (class "Default")
      (node (ref "GOUTH4") (pin "7") (pinfunction "7_7") (pintype "passive"))
      (node (ref "GSTP164") (pin "17") (pinfunction "~{OUT12}_17") (pintype "passive"))
    )
    (net (code "132") (name "/GOUT61") (class "Default")
      (node (ref "GOUTH4") (pin "15") (pinfunction "15_15") (pintype "passive"))
      (node (ref "GSTP164") (pin "18") (pinfunction "~{OUT13}_18") (pintype "passive"))
    )
    (net (code "133") (name "/GOUT62") (class "Default")
      (node (ref "GOUTH4") (pin "8") (pinfunction "8_8") (pintype "passive"))
      (node (ref "GSTP164") (pin "19") (pinfunction "~{OUT14}_19") (pintype "passive"))
    )
    (net (code "134") (name "/GOUT63") (class "Default")
      (node (ref "GOUTH4") (pin "16") (pinfunction "16_16") (pintype "passive"))
      (node (ref "GSTP164") (pin "20") (pinfunction "~{OUT15}_20") (pintype "passive"))
    )
    (net (code "135") (name "/GREENSPI") (class "Default")
      (node (ref "GSTP161") (pin "2") (pinfunction "SDI_2") (pintype "passive"))
      (node (ref "SPICOM") (pin "5") (pinfunction "5_5") (pintype "passive"))
    )
    (net (code "136") (name "/GREENSPIOUT1") (class "Default")
      (node (ref "GSTP161") (pin "22") (pinfunction "SDO_22") (pintype "passive"))
      (node (ref "GSTP162") (pin "2") (pinfunction "SDI_2") (pintype "passive"))
    )
    (net (code "137") (name "/GREENSPIOUT2") (class "Default")
      (node (ref "GSTP162") (pin "22") (pinfunction "SDO_22") (pintype "passive"))
      (node (ref "GSTP163") (pin "2") (pinfunction "SDI_2") (pintype "passive"))
    )
    (net (code "138") (name "/GREENSPIOUT3") (class "Default")
      (node (ref "GSTP163") (pin "22") (pinfunction "SDO_22") (pintype "passive"))
      (node (ref "GSTP164") (pin "2") (pinfunction "SDI_2") (pintype "passive"))
    )
    (net (code "139") (name "/L1S") (class "Default")
      (node (ref "LSIG") (pin "1") (pinfunction "1_1") (pintype "passive"))
      (node (ref "R13") (pin "1") (pinfunction "1_1") (pintype "passive"))
      (node (ref "R14") (pin "1") (pinfunction "1_1") (pintype "passive"))
    )
    (net (code "140") (name "/L2S") (class "Default")
      (node (ref "LSIG") (pin "2") (pinfunction "2_2") (pintype "passive"))
      (node (ref "R15") (pin "2") (pinfunction "2_2") (pintype "passive"))
      (node (ref "R16") (pin "2") (pinfunction "2_2") (pintype "passive"))
    )
    (net (code "141") (name "/L3S") (class "Default")
      (node (ref "LSIG") (pin "3") (pinfunction "3_3") (pintype "passive"))
      (node (ref "R17") (pin "1") (pinfunction "1_1") (pintype "passive"))
      (node (ref "R18") (pin "1") (pinfunction "1_1") (pintype "passive"))
    )
    (net (code "142") (name "/L4S") (class "Default")
      (node (ref "LSIG") (pin "4") (pinfunction "4_4") (pintype "passive"))
      (node (ref "R19") (pin "2") (pinfunction "2_2") (pintype "passive"))
      (node (ref "R20") (pin "2") (pinfunction "2_2") (pintype "passive"))
    )
    (net (code "143") (name "/L5S") (class "Default")
      (node (ref "LSIG") (pin "5") (pinfunction "5_5") (pintype "passive"))
      (node (ref "R21") (pin "1") (pinfunction "1_1") (pintype "passive"))
      (node (ref "R22") (pin "1") (pinfunction "1_1") (pintype "passive"))
    )
    (net (code "144") (name "/L6S") (class "Default")
      (node (ref "LSIG") (pin "6") (pinfunction "6_6") (pintype "passive"))
      (node (ref "R23") (pin "2") (pinfunction "2_2") (pintype "passive"))
      (node (ref "R24") (pin "2") (pinfunction "2_2") (pintype "passive"))
    )
    (net (code "145") (name "/L7S") (class "Default")
      (node (ref "LSIG") (pin "7") (pinfunction "7_7") (pintype "passive"))
      (node (ref "R25") (pin "1") (pinfunction "1_1") (pintype "passive"))
      (node (ref "R26") (pin "1") (pinfunction "1_1") (pintype "passive"))
    )
    (net (code "146") (name "/L8S") (class "Default")
      (node (ref "LSIG") (pin "8") (pinfunction "8_8") (pintype "passive"))
      (node (ref "R27") (pin "2") (pinfunction "2_2") (pintype "passive"))
      (node (ref "R28") (pin "2") (pinfunction "2_2") (pintype "passive"))
    )
    (net (code "147") (name "/LATCH") (class "Default")
      (node (ref "BSTP161") (pin "4") (pinfunction "LE/DM1_4") (pintype "passive"))
      (node (ref "BSTP162") (pin "4") (pinfunction "LE/DM1_4") (pintype "passive"))
      (node (ref "BSTP163") (pin "4") (pinfunction "LE/DM1_4") (pintype "passive"))
      (node (ref "BSTP164") (pin "4") (pinfunction "LE/DM1_4") (pintype "passive"))
      (node (ref "GSTP161") (pin "4") (pinfunction "LE/DM1_4") (pintype "passive"))
      (node (ref "GSTP162") (pin "4") (pinfunction "LE/DM1_4") (pintype "passive"))
      (node (ref "GSTP163") (pin "4") (pinfunction "LE/DM1_4") (pintype "passive"))
      (node (ref "GSTP164") (pin "4") (pinfunction "LE/DM1_4") (pintype "passive"))
      (node (ref "RSTP161") (pin "4") (pinfunction "LE/DM1_4") (pintype "passive"))
      (node (ref "RSTP162") (pin "4") (pinfunction "LE/DM1_4") (pintype "passive"))
      (node (ref "RSTP163") (pin "4") (pinfunction "LE/DM1_4") (pintype "passive"))
      (node (ref "RSTP164") (pin "4") (pinfunction "LE/DM1_4") (pintype "passive"))
      (node (ref "SPICOM") (pin "2") (pinfunction "2_2") (pintype "passive"))
    )
    (net (code "148") (name "/LAYER1") (class "Default")
      (node (ref "LOUT") (pin "1") (pinfunction "1_1") (pintype "passive"))
      (node (ref "PMOS1") (pin "7") (pinfunction "D1_7") (pintype "passive"))
      (node (ref "PMOS1") (pin "8") (pinfunction "D1_8") (pintype "passive"))
      (node (ref "R29") (pin "2") (pinfunction "2_2") (pintype "passive"))
    )
    (net (code "149") (name "/LAYER2") (class "Default")
      (node (ref "LOUT") (pin "2") (pinfunction "2_2") (pintype "passive"))
      (node (ref "PMOS1") (pin "5") (pinfunction "D2_5") (pintype "passive"))
      (node (ref "PMOS1") (pin "6") (pinfunction "D2_6") (pintype "passive"))
      (node (ref "R30") (pin "1") (pinfunction "1_1") (pintype "passive"))
    )
    (net (code "150") (name "/LAYER3") (class "Default")
      (node (ref "LOUT") (pin "3") (pinfunction "3_3") (pintype "passive"))
      (node (ref "PMOS2") (pin "7") (pinfunction "D1_7") (pintype "passive"))
      (node (ref "PMOS2") (pin "8") (pinfunction "D1_8") (pintype "passive"))
      (node (ref "R31") (pin "2") (pinfunction "2_2") (pintype "passive"))
    )
    (net (code "151") (name "/LAYER4") (class "Default")
      (node (ref "LOUT") (pin "4") (pinfunction "4_4") (pintype "passive"))
      (node (ref "PMOS2") (pin "5") (pinfunction "D2_5") (pintype "passive"))
      (node (ref "PMOS2") (pin "6") (pinfunction "D2_6") (pintype "passive"))
      (node (ref "R32") (pin "1") (pinfunction "1_1") (pintype "passive"))
    )
    (net (code "152") (name "/LAYER5") (class "Default")
      (node (ref "LOUT") (pin "5") (pinfunction "5_5") (pintype "passive"))
      (node (ref "PMOS3") (pin "7") (pinfunction "D1_7") (pintype "passive"))
      (node (ref "PMOS3") (pin "8") (pinfunction "D1_8") (pintype "passive"))
      (node (ref "R33") (pin "2") (pinfunction "2_2") (pintype "passive"))
    )
    (net (code "153") (name "/LAYER6") (class "Default")
      (node (ref "LOUT") (pin "6") (pinfunction "6_6") (pintype "passive"))
      (node (ref "PMOS3") (pin "5") (pinfunction "D2_5") (pintype "passive"))
      (node (ref "PMOS3") (pin "6") (pinfunction "D2_6") (pintype "passive"))
      (node (ref "R34") (pin "1") (pinfunction "1_1") (pintype "passive"))
    )
    (net (code "154") (name "/LAYER7") (class "Default")
      (node (ref "LOUT") (pin "7") (pinfunction "7_7") (pintype "passive"))
      (node (ref "PMOS4") (pin "7") (pinfunction "D1_7") (pintype "passive"))
      (node (ref "PMOS4") (pin "8") (pinfunction "D1_8") (pintype "passive"))
      (node (ref "R35") (pin "2") (pinfunction "2_2") (pintype "passive"))
    )
    (net (code "155") (name "/LAYER8") (class "Default")
      (node (ref "LOUT") (pin "8") (pinfunction "8_8") (pintype "passive"))
      (node (ref "PMOS4") (pin "5") (pinfunction "D2_5") (pintype "passive"))
      (node (ref "PMOS4") (pin "6") (pinfunction "D2_6") (pintype "passive"))
      (node (ref "R36") (pin "1") (pinfunction "1_1") (pintype "passive"))
    )
    (net (code "157") (name "/OENABLE") (class "Default")
      (node (ref "BSTP161") (pin "21") (pinfunction "~{OE/DM2}_21") (pintype "passive"))
      (node (ref "BSTP162") (pin "21") (pinfunction "~{OE/DM2}_21") (pintype "passive"))
      (node (ref "BSTP163") (pin "21") (pinfunction "~{OE/DM2}_21") (pintype "passive"))
      (node (ref "BSTP164") (pin "21") (pinfunction "~{OE/DM2}_21") (pintype "passive"))
      (node (ref "GSTP161") (pin "21") (pinfunction "~{OE/DM2}_21") (pintype "passive"))
      (node (ref "GSTP162") (pin "21") (pinfunction "~{OE/DM2}_21") (pintype "passive"))
      (node (ref "GSTP163") (pin "21") (pinfunction "~{OE/DM2}_21") (pintype "passive"))
      (node (ref "GSTP164") (pin "21") (pinfunction "~{OE/DM2}_21") (pintype "passive"))
      (node (ref "RSTP161") (pin "21") (pinfunction "~{OE/DM2}_21") (pintype "passive"))
      (node (ref "RSTP162") (pin "21") (pinfunction "~{OE/DM2}_21") (pintype "passive"))
      (node (ref "RSTP163") (pin "21") (pinfunction "~{OE/DM2}_21") (pintype "passive"))
      (node (ref "RSTP164") (pin "21") (pinfunction "~{OE/DM2}_21") (pintype "passive"))
      (node (ref "SPICOM") (pin "3") (pinfunction "3_3") (pintype "passive"))
    )
    (net (code "158") (name "/REDSPI") (class "Default")
      (node (ref "RSTP161") (pin "2") (pinfunction "SDI_2") (pintype "passive"))
      (node (ref "SPICOM") (pin "4") (pinfunction "4_4") (pintype "passive"))
    )
    (net (code "159") (name "/REDSPIOUT1") (class "Default")
      (node (ref "RSTP161") (pin "22") (pinfunction "SDO_22") (pintype "passive"))
      (node (ref "RSTP162") (pin "2") (pinfunction "SDI_2") (pintype "passive"))
    )
    (net (code "160") (name "/REDSPIOUT2") (class "Default")
      (node (ref "RSTP162") (pin "22") (pinfunction "SDO_22") (pintype "passive"))
      (node (ref "RSTP163") (pin "2") (pinfunction "SDI_2") (pintype "passive"))
    )
    (net (code "161") (name "/REDSPIOUT3") (class "Default")
      (node (ref "RSTP163") (pin "22") (pinfunction "SDO_22") (pintype "passive"))
      (node (ref "RSTP164") (pin "2") (pinfunction "SDI_2") (pintype "passive"))
    )
    (net (code "162") (name "/ROUT0") (class "Default")
      (node (ref "ROUTH1") (pin "1") (pinfunction "1_1") (pintype "passive"))
      (node (ref "RSTP161") (pin "5") (pinfunction "~{OUT0}_5") (pintype "passive"))
    )
    (net (code "163") (name "/ROUT1") (class "Default")
      (node (ref "ROUTH1") (pin "9") (pinfunction "9_9") (pintype "passive"))
      (node (ref "RSTP161") (pin "6") (pinfunction "~{OUT1}_6") (pintype "passive"))
    )
    (net (code "164") (name "/ROUT2") (class "Default")
      (node (ref "ROUTH1") (pin "2") (pinfunction "2_2") (pintype "passive"))
      (node (ref "RSTP161") (pin "7") (pinfunction "~{OUT2}_7") (pintype "passive"))
    )
    (net (code "165") (name "/ROUT3") (class "Default")
      (node (ref "ROUTH1") (pin "10") (pinfunction "10_10") (pintype "passive"))
      (node (ref "RSTP161") (pin "8") (pinfunction "~{OUT3}_8") (pintype "passive"))
    )
    (net (code "166") (name "/ROUT4") (class "Default")
      (node (ref "ROUTH1") (pin "3") (pinfunction "3_3") (pintype "passive"))
      (node (ref "RSTP161") (pin "9") (pinfunction "~{OUT4}_9") (pintype "passive"))
    )
    (net (code "167") (name "/ROUT5") (class "Default")
      (node (ref "ROUTH1") (pin "11") (pinfunction "11_11") (pintype "passive"))
      (node (ref "RSTP161") (pin "10") (pinfunction "~{OUT5}_10") (pintype "passive"))
    )
    (net (code "168") (name "/ROUT6") (class "Default")
      (node (ref "ROUTH1") (pin "4") (pinfunction "4_4") (pintype "passive"))
      (node (ref "RSTP161") (pin "11") (pinfunction "~{OUT6}_11") (pintype "passive"))
    )
    (net (code "169") (name "/ROUT7") (class "Default")
      (node (ref "ROUTH1") (pin "12") (pinfunction "12_12") (pintype "passive"))
      (node (ref "RSTP161") (pin "12") (pinfunction "~{OUT7}_12") (pintype "passive"))
    )
    (net (code "170") (name "/ROUT8") (class "Default")
      (node (ref "ROUTH1") (pin "5") (pinfunction "5_5") (pintype "passive"))
      (node (ref "RSTP161") (pin "13") (pinfunction "~{OUT8}_13") (pintype "passive"))
    )
    (net (code "171") (name "/ROUT9") (class "Default")
      (node (ref "ROUTH1") (pin "13") (pinfunction "13_13") (pintype "passive"))
      (node (ref "RSTP161") (pin "14") (pinfunction "~{OUT9}_14") (pintype "passive"))
    )
    (net (code "172") (name "/ROUT10") (class "Default")
      (node (ref "ROUTH1") (pin "6") (pinfunction "6_6") (pintype "passive"))
      (node (ref "RSTP161") (pin "15") (pinfunction "~{OUT10}_15") (pintype "passive"))
    )
    (net (code "173") (name "/ROUT11") (class "Default")
      (node (ref "ROUTH1") (pin "14") (pinfunction "14_14") (pintype "passive"))
      (node (ref "RSTP161") (pin "16") (pinfunction "~{OUT11}_16") (pintype "passive"))
    )
    (net (code "174") (name "/ROUT12") (class "Default")
      (node (ref "ROUTH1") (pin "7") (pinfunction "7_7") (pintype "passive"))
      (node (ref "RSTP161") (pin "17") (pinfunction "~{OUT12}_17") (pintype "passive"))
    )
    (net (code "175") (name "/ROUT13") (class "Default")
      (node (ref "ROUTH1") (pin "15") (pinfunction "15_15") (pintype "passive"))
      (node (ref "RSTP161") (pin "18") (pinfunction "~{OUT13}_18") (pintype "passive"))
    )
    (net (code "176") (name "/ROUT14") (class "Default")
      (node (ref "ROUTH1") (pin "8") (pinfunction "8_8") (pintype "passive"))
      (node (ref "RSTP161") (pin "19") (pinfunction "~{OUT14}_19") (pintype "passive"))
    )
    (net (code "177") (name "/ROUT15") (class "Default")
      (node (ref "ROUTH1") (pin "16") (pinfunction "16_16") (pintype "passive"))
      (node (ref "RSTP161") (pin "20") (pinfunction "~{OUT15}_20") (pintype "passive"))
    )
    (net (code "178") (name "/ROUT16") (class "Default")
      (node (ref "ROUTH2") (pin "1") (pinfunction "1_1") (pintype "passive"))
      (node (ref "RSTP162") (pin "5") (pinfunction "~{OUT0}_5") (pintype "passive"))
    )
    (net (code "179") (name "/ROUT17") (class "Default")
      (node (ref "ROUTH2") (pin "9") (pinfunction "9_9") (pintype "passive"))
      (node (ref "RSTP162") (pin "6") (pinfunction "~{OUT1}_6") (pintype "passive"))
    )
    (net (code "180") (name "/ROUT18") (class "Default")
      (node (ref "ROUTH2") (pin "2") (pinfunction "2_2") (pintype "passive"))
      (node (ref "RSTP162") (pin "7") (pinfunction "~{OUT2}_7") (pintype "passive"))
    )
    (net (code "181") (name "/ROUT19") (class "Default")
      (node (ref "ROUTH2") (pin "10") (pinfunction "10_10") (pintype "passive"))
      (node (ref "RSTP162") (pin "8") (pinfunction "~{OUT3}_8") (pintype "passive"))
    )
    (net (code "182") (name "/ROUT20") (class "Default")
      (node (ref "ROUTH2") (pin "3") (pinfunction "3_3") (pintype "passive"))
      (node (ref "RSTP162") (pin "9") (pinfunction "~{OUT4}_9") (pintype "passive"))
    )
    (net (code "183") (name "/ROUT21") (class "Default")
      (node (ref "ROUTH2") (pin "11") (pinfunction "11_11") (pintype "passive"))
      (node (ref "RSTP162") (pin "10") (pinfunction "~{OUT5}_10") (pintype "passive"))
    )
    (net (code "184") (name "/ROUT22") (class "Default")
      (node (ref "ROUTH2") (pin "4") (pinfunction "4_4") (pintype "passive"))
      (node (ref "RSTP162") (pin "11") (pinfunction "~{OUT6}_11") (pintype "passive"))
    )
    (net (code "185") (name "/ROUT23") (class "Default")
      (node (ref "ROUTH2") (pin "12") (pinfunction "12_12") (pintype "passive"))
      (node (ref "RSTP162") (pin "12") (pinfunction "~{OUT7}_12") (pintype "passive"))
    )
    (net (code "186") (name "/ROUT24") (class "Default")
      (node (ref "ROUTH2") (pin "5") (pinfunction "5_5") (pintype "passive"))
      (node (ref "RSTP162") (pin "13") (pinfunction "~{OUT8}_13") (pintype "passive"))
    )
    (net (code "187") (name "/ROUT25") (class "Default")
      (node (ref "ROUTH2") (pin "13") (pinfunction "13_13") (pintype "passive"))
      (node (ref "RSTP162") (pin "14") (pinfunction "~{OUT9}_14") (pintype "passive"))
    )
    (net (code "188") (name "/ROUT26") (class "Default")
      (node (ref "ROUTH2") (pin "6") (pinfunction "6_6") (pintype "passive"))
      (node (ref "RSTP162") (pin "15") (pinfunction "~{OUT10}_15") (pintype "passive"))
    )
    (net (code "189") (name "/ROUT27") (class "Default")
      (node (ref "ROUTH2") (pin "14") (pinfunction "14_14") (pintype "passive"))
      (node (ref "RSTP162") (pin "16") (pinfunction "~{OUT11}_16") (pintype "passive"))
    )
    (net (code "190") (name "/ROUT28") (class "Default")
      (node (ref "ROUTH2") (pin "7") (pinfunction "7_7") (pintype "passive"))
      (node (ref "RSTP162") (pin "17") (pinfunction "~{OUT12}_17") (pintype "passive"))
    )
    (net (code "191") (name "/ROUT29") (class "Default")
      (node (ref "ROUTH2") (pin "15") (pinfunction "15_15") (pintype "passive"))
      (node (ref "RSTP162") (pin "18") (pinfunction "~{OUT13}_18") (pintype "passive"))
    )
    (net (code "192") (name "/ROUT30") (class "Default")
      (node (ref "ROUTH2") (pin "8") (pinfunction "8_8") (pintype "passive"))
      (node (ref "RSTP162") (pin "19") (pinfunction "~{OUT14}_19") (pintype "passive"))
    )
    (net (code "193") (name "/ROUT31") (class "Default")
      (node (ref "ROUTH2") (pin "16") (pinfunction "16_16") (pintype "passive"))
      (node (ref "RSTP162") (pin "20") (pinfunction "~{OUT15}_20") (pintype "passive"))
    )
    (net (code "194") (name "/ROUT32") (class "Default")
      (node (ref "ROUTH3") (pin "1") (pinfunction "1_1") (pintype "passive"))
      (node (ref "RSTP163") (pin "5") (pinfunction "~{OUT0}_5") (pintype "passive"))
    )
    (net (code "195") (name "/ROUT33") (class "Default")
      (node (ref "ROUTH3") (pin "9") (pinfunction "9_9") (pintype "passive"))
      (node (ref "RSTP163") (pin "6") (pinfunction "~{OUT1}_6") (pintype "passive"))
    )
    (net (code "196") (name "/ROUT34") (class "Default")
      (node (ref "ROUTH3") (pin "2") (pinfunction "2_2") (pintype "passive"))
      (node (ref "RSTP163") (pin "7") (pinfunction "~{OUT2}_7") (pintype "passive"))
    )
    (net (code "197") (name "/ROUT35") (class "Default")
      (node (ref "ROUTH3") (pin "10") (pinfunction "10_10") (pintype "passive"))
      (node (ref "RSTP163") (pin "8") (pinfunction "~{OUT3}_8") (pintype "passive"))
    )
    (net (code "198") (name "/ROUT36") (class "Default")
      (node (ref "ROUTH3") (pin "3") (pinfunction "3_3") (pintype "passive"))
      (node (ref "RSTP163") (pin "9") (pinfunction "~{OUT4}_9") (pintype "passive"))
    )
    (net (code "199") (name "/ROUT37") (class "Default")
      (node (ref "ROUTH3") (pin "11") (pinfunction "11_11") (pintype "passive"))
      (node (ref "RSTP163") (pin "10") (pinfunction "~{OUT5}_10") (pintype "passive"))
    )
    (net (code "200") (name "/ROUT38") (class "Default")
      (node (ref "ROUTH3") (pin "4") (pinfunction "4_4") (pintype "passive"))
      (node (ref "RSTP163") (pin "11") (pinfunction "~{OUT6}_11") (pintype "passive"))
    )
    (net (code "201") (name "/ROUT39") (class "Default")
      (node (ref "ROUTH3") (pin "12") (pinfunction "12_12") (pintype "passive"))
      (node (ref "RSTP163") (pin "12") (pinfunction "~{OUT7}_12") (pintype "passive"))
    )
    (net (code "202") (name "/ROUT40") (class "Default")
      (node (ref "ROUTH3") (pin "5") (pinfunction "5_5") (pintype "passive"))
      (node (ref "RSTP163") (pin "13") (pinfunction "~{OUT8}_13") (pintype "passive"))
    )
    (net (code "203") (name "/ROUT41") (class "Default")
      (node (ref "ROUTH3") (pin "13") (pinfunction "13_13") (pintype "passive"))
      (node (ref "RSTP163") (pin "14") (pinfunction "~{OUT9}_14") (pintype "passive"))
    )
    (net (code "204") (name "/ROUT42") (class "Default")
      (node (ref "ROUTH3") (pin "6") (pinfunction "6_6") (pintype "passive"))
      (node (ref "RSTP163") (pin "15") (pinfunction "~{OUT10}_15") (pintype "passive"))
    )
    (net (code "205") (name "/ROUT43") (class "Default")
      (node (ref "ROUTH3") (pin "14") (pinfunction "14_14") (pintype "passive"))
      (node (ref "RSTP163") (pin "16") (pinfunction "~{OUT11}_16") (pintype "passive"))
    )
    (net (code "206") (name "/ROUT44") (class "Default")
      (node (ref "ROUTH3") (pin "7") (pinfunction "7_7") (pintype "passive"))
      (node (ref "RSTP163") (pin "17") (pinfunction "~{OUT12}_17") (pintype "passive"))
    )
    (net (code "207") (name "/ROUT45") (class "Default")
      (node (ref "ROUTH3") (pin "15") (pinfunction "15_15") (pintype "passive"))
      (node (ref "RSTP163") (pin "18") (pinfunction "~{OUT13}_18") (pintype "passive"))
    )
    (net (code "208") (name "/ROUT46") (class "Default")
      (node (ref "ROUTH3") (pin "8") (pinfunction "8_8") (pintype "passive"))
      (node (ref "RSTP163") (pin "19") (pinfunction "~{OUT14}_19") (pintype "passive"))
    )
    (net (code "209") (name "/ROUT47") (class "Default")
      (node (ref "ROUTH3") (pin "16") (pinfunction "16_16") (pintype "passive"))
      (node (ref "RSTP163") (pin "20") (pinfunction "~{OUT15}_20") (pintype "passive"))
    )
    (net (code "210") (name "/ROUT48") (class "Default")
      (node (ref "ROUTH4") (pin "1") (pinfunction "1_1") (pintype "passive"))
      (node (ref "RSTP164") (pin "5") (pinfunction "~{OUT0}_5") (pintype "passive"))
    )
    (net (code "211") (name "/ROUT49") (class "Default")
      (node (ref "ROUTH4") (pin "9") (pinfunction "9_9") (pintype "passive"))
      (node (ref "RSTP164") (pin "6") (pinfunction "~{OUT1}_6") (pintype "passive"))
    )
    (net (code "212") (name "/ROUT50") (class "Default")
      (node (ref "ROUTH4") (pin "2") (pinfunction "2_2") (pintype "passive"))
      (node (ref "RSTP164") (pin "7") (pinfunction "~{OUT2}_7") (pintype "passive"))
    )
    (net (code "213") (name "/ROUT51") (class "Default")
      (node (ref "ROUTH4") (pin "10") (pinfunction "10_10") (pintype "passive"))
      (node (ref "RSTP164") (pin "8") (pinfunction "~{OUT3}_8") (pintype "passive"))
    )
    (net (code "214") (name "/ROUT52") (class "Default")
      (node (ref "ROUTH4") (pin "3") (pinfunction "3_3") (pintype "passive"))
      (node (ref "RSTP164") (pin "9") (pinfunction "~{OUT4}_9") (pintype "passive"))
    )
    (net (code "215") (name "/ROUT53") (class "Default")
      (node (ref "ROUTH4") (pin "11") (pinfunction "11_11") (pintype "passive"))
      (node (ref "RSTP164") (pin "10") (pinfunction "~{OUT5}_10") (pintype "passive"))
    )
    (net (code "216") (name "/ROUT54") (class "Default")
      (node (ref "ROUTH4") (pin "4") (pinfunction "4_4") (pintype "passive"))
      (node (ref "RSTP164") (pin "11") (pinfunction "~{OUT6}_11") (pintype "passive"))
    )
    (net (code "217") (name "/ROUT55") (class "Default")
      (node (ref "ROUTH4") (pin "12") (pinfunction "12_12") (pintype "passive"))
      (node (ref "RSTP164") (pin "12") (pinfunction "~{OUT7}_12") (pintype "passive"))
    )
    (net (code "218") (name "/ROUT56") (class "Default")
      (node (ref "ROUTH4") (pin "5") (pinfunction "5_5") (pintype "passive"))
      (node (ref "RSTP164") (pin "13") (pinfunction "~{OUT8}_13") (pintype "passive"))
    )
    (net (code "219") (name "/ROUT57") (class "Default")
      (node (ref "ROUTH4") (pin "13") (pinfunction "13_13") (pintype "passive"))
      (node (ref "RSTP164") (pin "14") (pinfunction "~{OUT9}_14") (pintype "passive"))
    )
    (net (code "220") (name "/ROUT58") (class "Default")
      (node (ref "ROUTH4") (pin "6") (pinfunction "6_6") (pintype "passive"))
      (node (ref "RSTP164") (pin "15") (pinfunction "~{OUT10}_15") (pintype "passive"))
    )
    (net (code "221") (name "/ROUT59") (class "Default")
      (node (ref "ROUTH4") (pin "14") (pinfunction "14_14") (pintype "passive"))
      (node (ref "RSTP164") (pin "16") (pinfunction "~{OUT11}_16") (pintype "passive"))
    )
    (net (code "222") (name "/ROUT60") (class "Default")
      (node (ref "ROUTH4") (pin "7") (pinfunction "7_7") (pintype "passive"))
      (node (ref "RSTP164") (pin "17") (pinfunction "~{OUT12}_17") (pintype "passive"))
    )
    (net (code "223") (name "/ROUT61") (class "Default")
      (node (ref "ROUTH4") (pin "15") (pinfunction "15_15") (pintype "passive"))
      (node (ref "RSTP164") (pin "18") (pinfunction "~{OUT13}_18") (pintype "passive"))
    )
    (net (code "224") (name "/ROUT62") (class "Default")
      (node (ref "ROUTH4") (pin "8") (pinfunction "8_8") (pintype "passive"))
      (node (ref "RSTP164") (pin "19") (pinfunction "~{OUT14}_19") (pintype "passive"))
    )
    (net (code "225") (name "/ROUT63") (class "Default")
      (node (ref "ROUTH4") (pin "16") (pinfunction "16_16") (pintype "passive"))
      (node (ref "RSTP164") (pin "20") (pinfunction "~{OUT15}_20") (pintype "passive"))
    )
    (net (code "226") (name "GND") (class "Default")
      (node (ref "BSTP161") (pin "1") (pinfunction "GND_1") (pintype "passive"))
      (node (ref "BSTP162") (pin "1") (pinfunction "GND_1") (pintype "passive"))
      (node (ref "BSTP163") (pin "1") (pinfunction "GND_1") (pintype "passive"))
      (node (ref "BSTP164") (pin "1") (pinfunction "GND_1") (pintype "passive"))
      (node (ref "C1") (pin "1") (pinfunction "1_1") (pintype "passive"))
      (node (ref "C10") (pin "1") (pinfunction "1_1") (pintype "passive"))
      (node (ref "C11") (pin "1") (pinfunction "1_1") (pintype "passive"))
      (node (ref "C12") (pin "1") (pinfunction "1_1") (pintype "passive"))
      (node (ref "C2") (pin "1") (pinfunction "1_1") (pintype "passive"))
      (node (ref "C3") (pin "1") (pinfunction "1_1") (pintype "passive"))
      (node (ref "C4") (pin "1") (pinfunction "1_1") (pintype "passive"))
      (node (ref "C5") (pin "1") (pinfunction "1_1") (pintype "passive"))
      (node (ref "C6") (pin "1") (pinfunction "1_1") (pintype "passive"))
      (node (ref "C7") (pin "1") (pinfunction "1_1") (pintype "passive"))
      (node (ref "C8") (pin "1") (pinfunction "1_1") (pintype "passive"))
      (node (ref "C9") (pin "1") (pinfunction "1_1") (pintype "passive"))
      (node (ref "GSTP161") (pin "1") (pinfunction "GND_1") (pintype "passive"))
      (node (ref "GSTP162") (pin "1") (pinfunction "GND_1") (pintype "passive"))
      (node (ref "GSTP163") (pin "1") (pinfunction "GND_1") (pintype "passive"))
      (node (ref "GSTP164") (pin "1") (pinfunction "GND_1") (pintype "passive"))
      (node (ref "R1") (pin "2") (pinfunction "2_2") (pintype "passive"))
      (node (ref "R10") (pin "2") (pinfunction "2_2") (pintype "passive"))
      (node (ref "R11") (pin "2") (pinfunction "2_2") (pintype "passive"))
      (node (ref "R12") (pin "2") (pinfunction "2_2") (pintype "passive"))
      (node (ref "R2") (pin "2") (pinfunction "2_2") (pintype "passive"))
      (node (ref "R29") (pin "1") (pinfunction "1_1") (pintype "passive"))
      (node (ref "R3") (pin "2") (pinfunction "2_2") (pintype "passive"))
      (node (ref "R30") (pin "2") (pinfunction "2_2") (pintype "passive"))
      (node (ref "R31") (pin "1") (pinfunction "1_1") (pintype "passive"))
      (node (ref "R32") (pin "2") (pinfunction "2_2") (pintype "passive"))
      (node (ref "R33") (pin "1") (pinfunction "1_1") (pintype "passive"))
      (node (ref "R34") (pin "2") (pinfunction "2_2") (pintype "passive"))
      (node (ref "R35") (pin "1") (pinfunction "1_1") (pintype "passive"))
      (node (ref "R36") (pin "2") (pinfunction "2_2") (pintype "passive"))
      (node (ref "R4") (pin "2") (pinfunction "2_2") (pintype "passive"))
      (node (ref "R5") (pin "2") (pinfunction "2_2") (pintype "passive"))
      (node (ref "R6") (pin "2") (pinfunction "2_2") (pintype "passive"))
      (node (ref "R7") (pin "2") (pinfunction "2_2") (pintype "passive"))
      (node (ref "R8") (pin "2") (pinfunction "2_2") (pintype "passive"))
      (node (ref "R9") (pin "2") (pinfunction "2_2") (pintype "passive"))
      (node (ref "RSTP161") (pin "1") (pinfunction "GND_1") (pintype "passive"))
      (node (ref "RSTP162") (pin "1") (pinfunction "GND_1") (pintype "passive"))
      (node (ref "RSTP163") (pin "1") (pinfunction "GND_1") (pintype "passive"))
      (node (ref "RSTP164") (pin "1") (pinfunction "GND_1") (pintype "passive"))
      (node (ref "Terminal Block") (pin "3") (pinfunction "pin3_3") (pintype "passive"))
    )
    (net (code "227") (name "Net-(BSTP161-R-EXT)") (class "Default")
      (node (ref "BSTP161") (pin "23") (pinfunction "R-EXT_23") (pintype "passive"))
      (node (ref "R9") (pin "1") (pinfunction "1_1") (pintype "passive"))
    )
    (net (code "228") (name "Net-(BSTP162-R-EXT)") (class "Default")
      (node (ref "BSTP162") (pin "23") (pinfunction "R-EXT_23") (pintype "passive"))
      (node (ref "R10") (pin "1") (pinfunction "1_1") (pintype "passive"))
    )
    (net (code "229") (name "Net-(BSTP163-R-EXT)") (class "Default")
      (node (ref "BSTP163") (pin "23") (pinfunction "R-EXT_23") (pintype "passive"))
      (node (ref "R11") (pin "1") (pinfunction "1_1") (pintype "passive"))
    )
    (net (code "230") (name "Net-(BSTP164-R-EXT)") (class "Default")
      (node (ref "BSTP164") (pin "23") (pinfunction "R-EXT_23") (pintype "passive"))
      (node (ref "R12") (pin "1") (pinfunction "1_1") (pintype "passive"))
    )
    (net (code "231") (name "Net-(GSTP161-R-EXT)") (class "Default")
      (node (ref "GSTP161") (pin "23") (pinfunction "R-EXT_23") (pintype "passive"))
      (node (ref "R5") (pin "1") (pinfunction "1_1") (pintype "passive"))
    )
    (net (code "232") (name "Net-(GSTP162-R-EXT)") (class "Default")
      (node (ref "GSTP162") (pin "23") (pinfunction "R-EXT_23") (pintype "passive"))
      (node (ref "R6") (pin "1") (pinfunction "1_1") (pintype "passive"))
    )
    (net (code "233") (name "Net-(GSTP163-R-EXT)") (class "Default")
      (node (ref "GSTP163") (pin "23") (pinfunction "R-EXT_23") (pintype "passive"))
      (node (ref "R7") (pin "1") (pinfunction "1_1") (pintype "passive"))
    )
    (net (code "234") (name "Net-(GSTP164-R-EXT)") (class "Default")
      (node (ref "GSTP164") (pin "23") (pinfunction "R-EXT_23") (pintype "passive"))
      (node (ref "R8") (pin "1") (pinfunction "1_1") (pintype "passive"))
    )
    (net (code "235") (name "Net-(PMOS1-G1)") (class "Default")
      (node (ref "PMOS1") (pin "2") (pinfunction "G1_2") (pintype "passive"))
      (node (ref "R14") (pin "2") (pinfunction "2_2") (pintype "passive"))
    )
    (net (code "236") (name "Net-(PMOS1-G2)") (class "Default")
      (node (ref "PMOS1") (pin "4") (pinfunction "G2_4") (pintype "passive"))
      (node (ref "R16") (pin "1") (pinfunction "1_1") (pintype "passive"))
    )
    (net (code "237") (name "Net-(PMOS2-G1)") (class "Default")
      (node (ref "PMOS2") (pin "2") (pinfunction "G1_2") (pintype "passive"))
      (node (ref "R18") (pin "2") (pinfunction "2_2") (pintype "passive"))
    )
    (net (code "238") (name "Net-(PMOS2-G2)") (class "Default")
      (node (ref "PMOS2") (pin "4") (pinfunction "G2_4") (pintype "passive"))
      (node (ref "R20") (pin "1") (pinfunction "1_1") (pintype "passive"))
    )
    (net (code "239") (name "Net-(PMOS3-G1)") (class "Default")
      (node (ref "PMOS3") (pin "2") (pinfunction "G1_2") (pintype "passive"))
      (node (ref "R22") (pin "2") (pinfunction "2_2") (pintype "passive"))
    )
    (net (code "240") (name "Net-(PMOS3-G2)") (class "Default")
      (node (ref "PMOS3") (pin "4") (pinfunction "G2_4") (pintype "passive"))
      (node (ref "R24") (pin "1") (pinfunction "1_1") (pintype "passive"))
    )
    (net (code "241") (name "Net-(PMOS4-G1)") (class "Default")
      (node (ref "PMOS4") (pin "2") (pinfunction "G1_2") (pintype "passive"))
      (node (ref "R26") (pin "2") (pinfunction "2_2") (pintype "passive"))
    )
    (net (code "242") (name "Net-(PMOS4-G2)") (class "Default")
      (node (ref "PMOS4") (pin "4") (pinfunction "G2_4") (pintype "passive"))
      (node (ref "R28") (pin "1") (pinfunction "1_1") (pintype "passive"))
    )
    (net (code "243") (name "Net-(RSTP161-R-EXT)") (class "Default")
      (node (ref "R1") (pin "1") (pinfunction "1_1") (pintype "passive"))
      (node (ref "RSTP161") (pin "23") (pinfunction "R-EXT_23") (pintype "passive"))
    )
    (net (code "244") (name "Net-(RSTP162-R-EXT)") (class "Default")
      (node (ref "R2") (pin "1") (pinfunction "1_1") (pintype "passive"))
      (node (ref "RSTP162") (pin "23") (pinfunction "R-EXT_23") (pintype "passive"))
    )
    (net (code "245") (name "Net-(RSTP163-R-EXT)") (class "Default")
      (node (ref "R3") (pin "1") (pinfunction "1_1") (pintype "passive"))
      (node (ref "RSTP163") (pin "23") (pinfunction "R-EXT_23") (pintype "passive"))
    )
    (net (code "246") (name "Net-(RSTP164-R-EXT)") (class "Default")
      (node (ref "R4") (pin "1") (pinfunction "1_1") (pintype "passive"))
      (node (ref "RSTP164") (pin "23") (pinfunction "R-EXT_23") (pintype "passive"))
    )
    (net (code "247") (name "unconnected-(BSTP164-SDO-Pad22)") (class "Default")
      (node (ref "BSTP164") (pin "22") (pinfunction "SDO_22") (pintype "passive"))
    )
    (net (code "248") (name "unconnected-(GSTP164-SDO-Pad22)") (class "Default")
      (node (ref "GSTP164") (pin "22") (pinfunction "SDO_22") (pintype "passive"))
    )
    (net (code "249") (name "unconnected-(RSTP164-SDO-Pad22)") (class "Default")
      (node (ref "RSTP164") (pin "22") (pinfunction "SDO_22") (pintype "passive"))
    )
    (net (code "250") (name "unconnected-(SPICOM-Pad7)") (class "Default")
      (node (ref "SPICOM") (pin "7") (pinfunction "7_7") (pintype "passive"))
    )
    (net (code "251") (name "unconnected-(SPICOM-Pad8)") (class "Default")
      (node (ref "SPICOM") (pin "8") (pinfunction "8_8") (pintype "passive"))
    )
    (net (code "252") (name "unconnected-(Terminal Block-pin2-Pad2)") (class "Default")
      (node (ref "Terminal Block") (pin "2") (pinfunction "pin2_2") (pintype "passive"))
    )
  )
)
